# RX8I.net
KiCad netlist of a schematic drawn in EAGLE
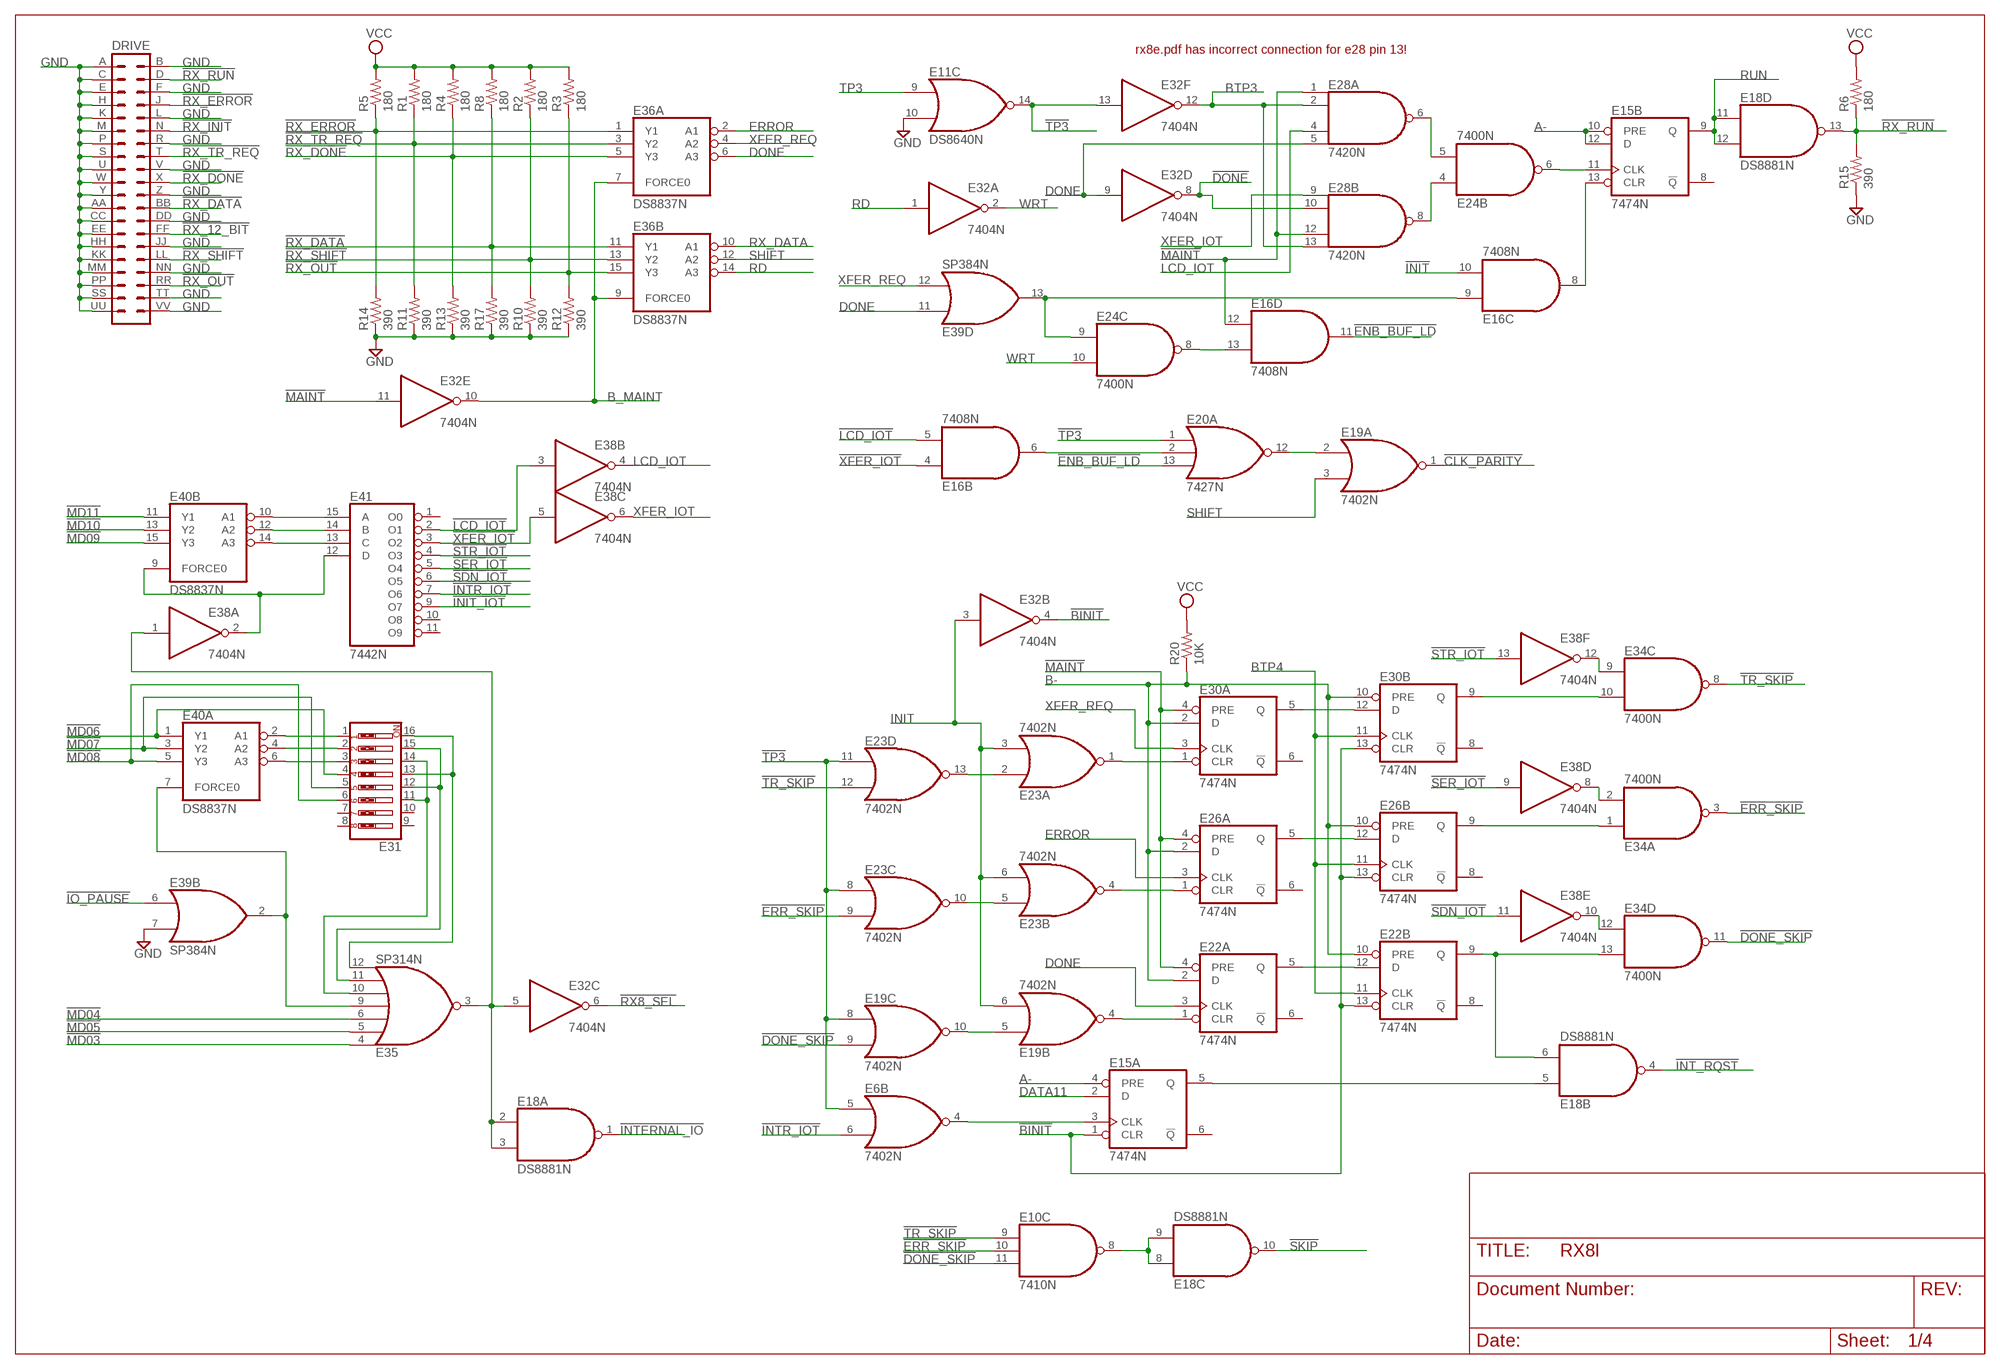
[diagram p0: schematic, sheet 1]
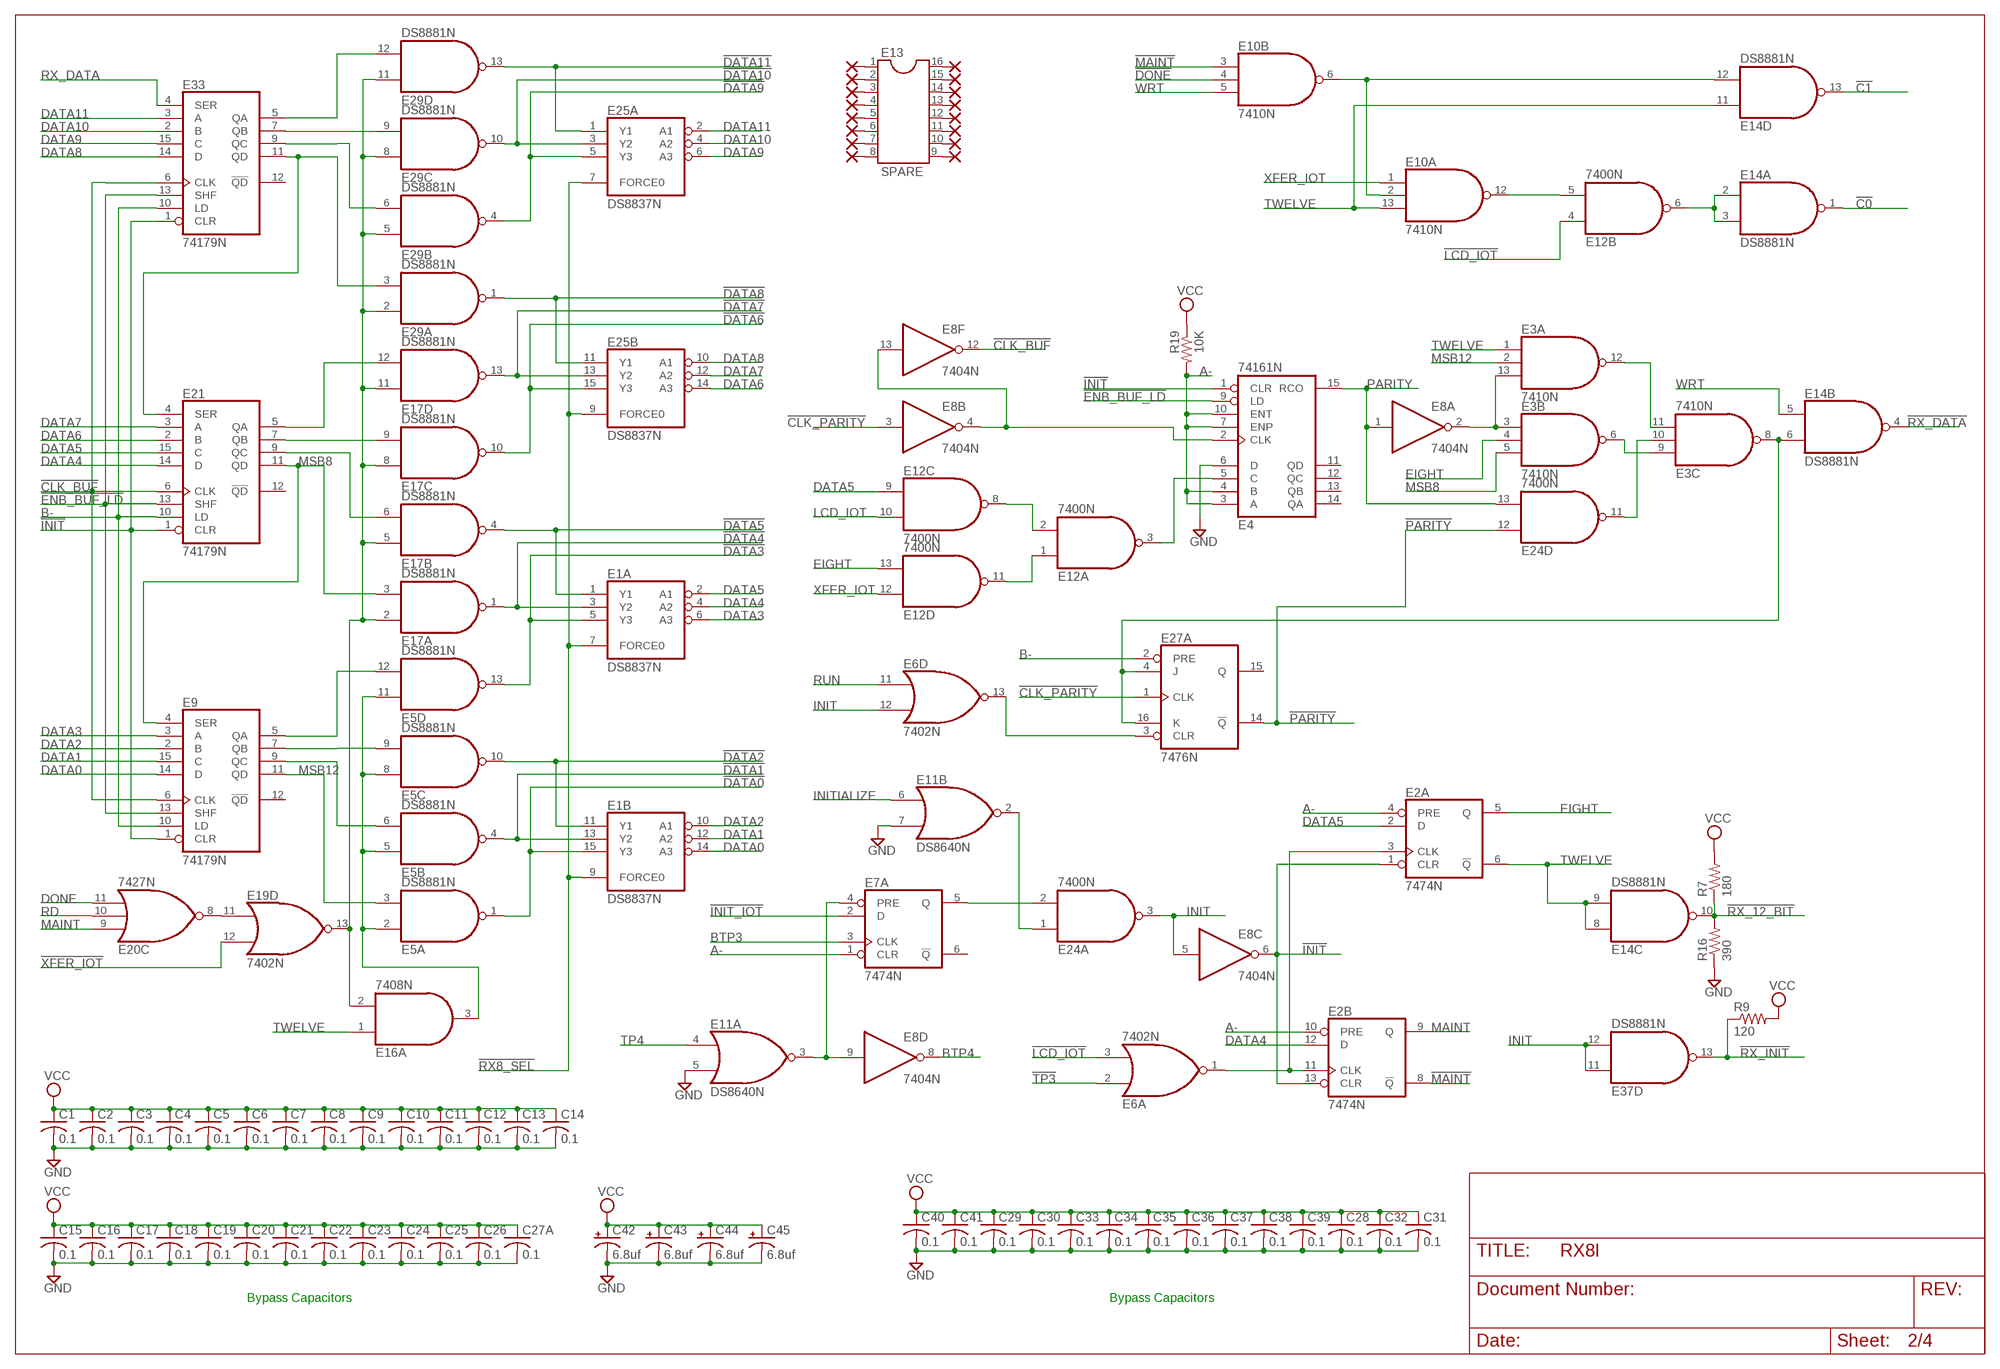
[diagram p1: schematic, sheet 2]
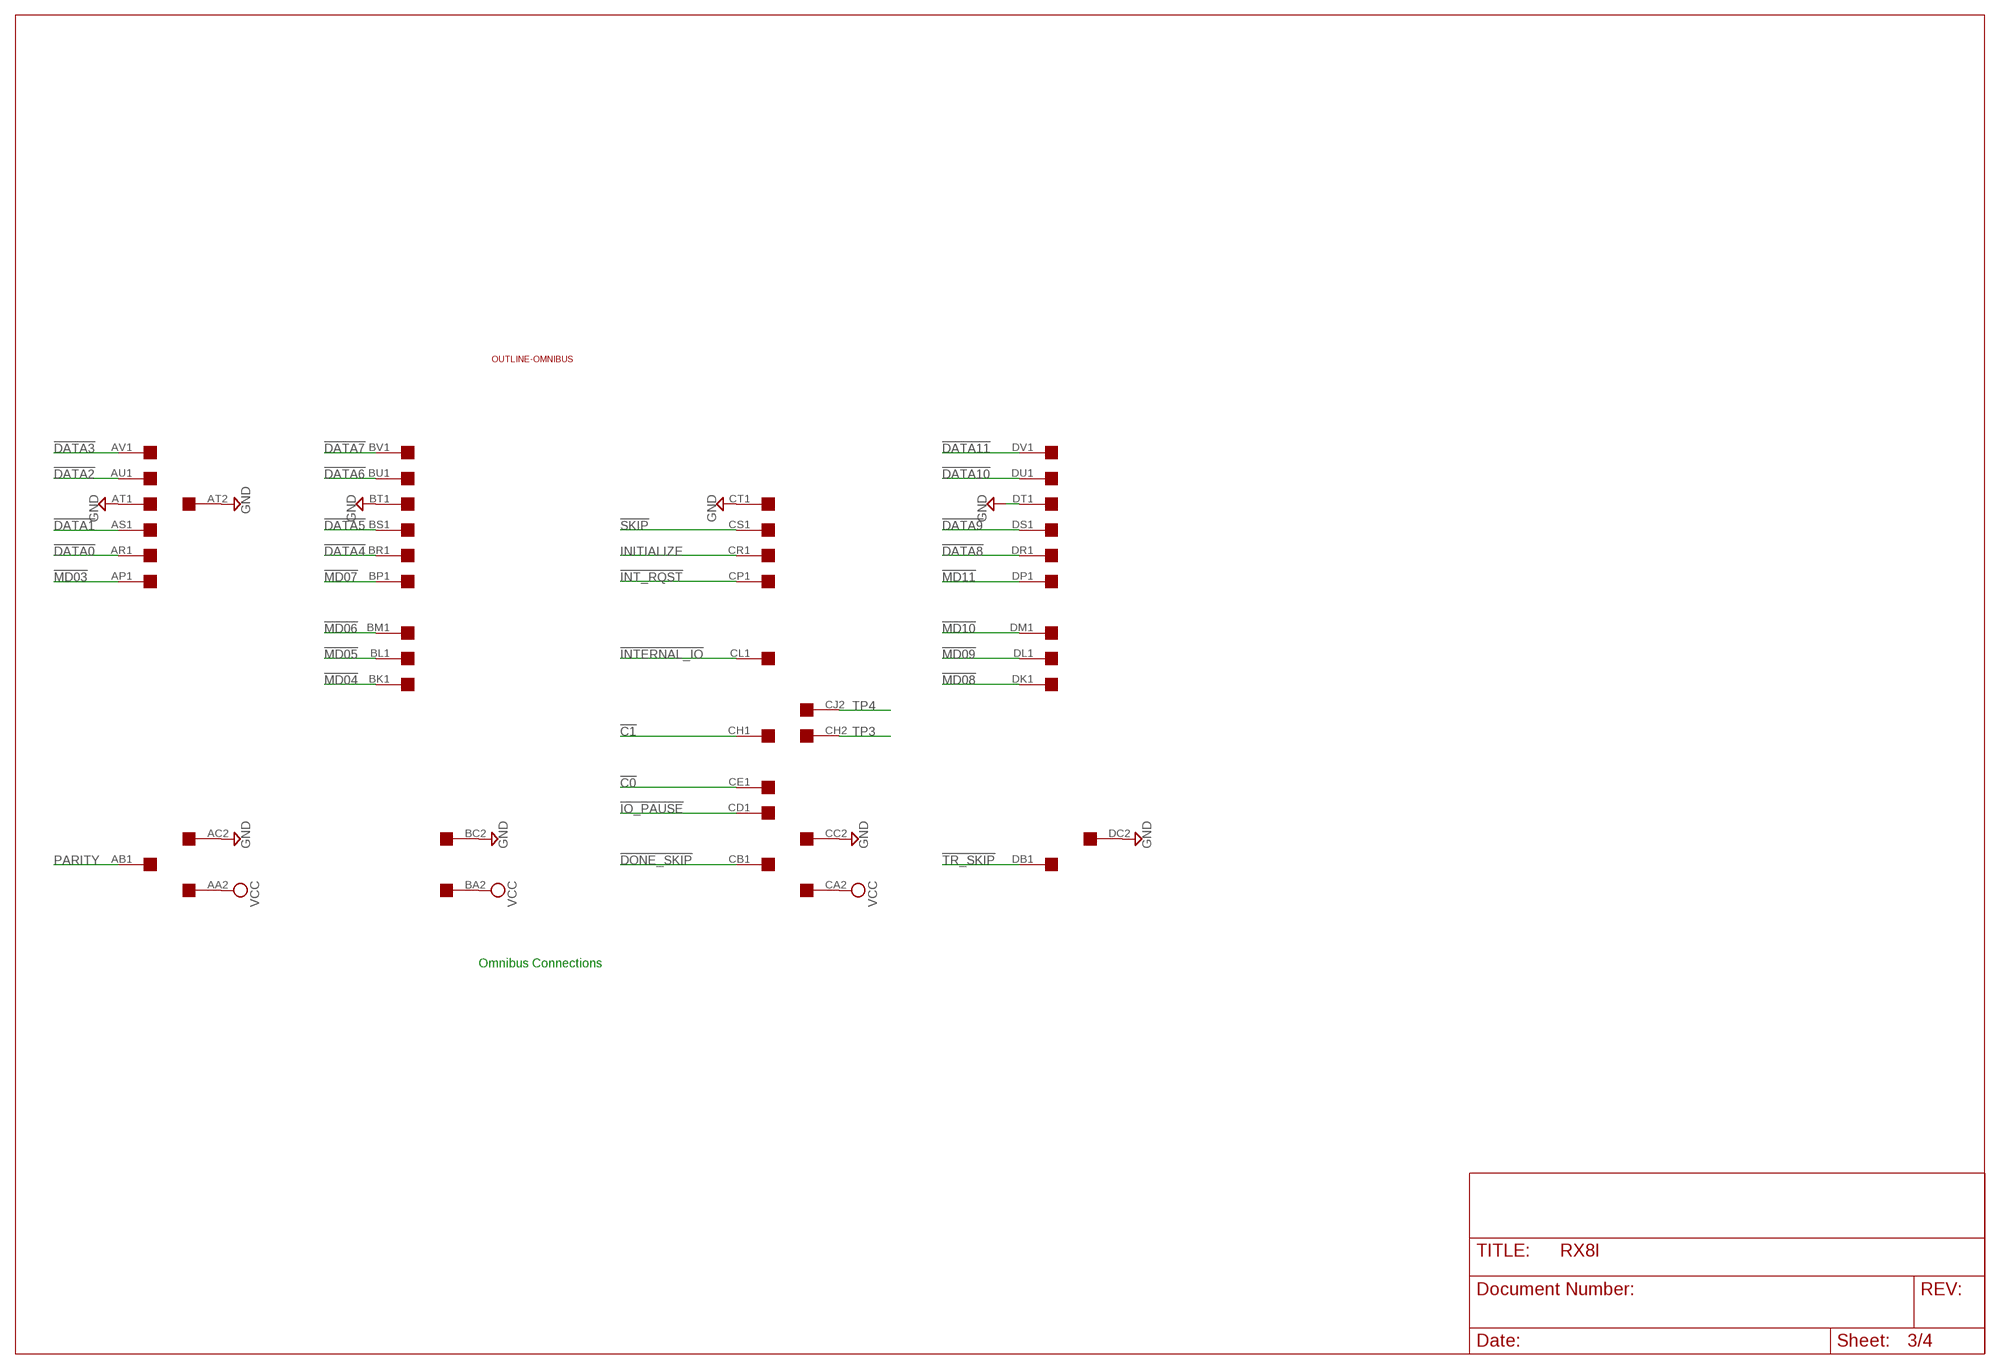
[diagram p2: schematic, sheet 3]
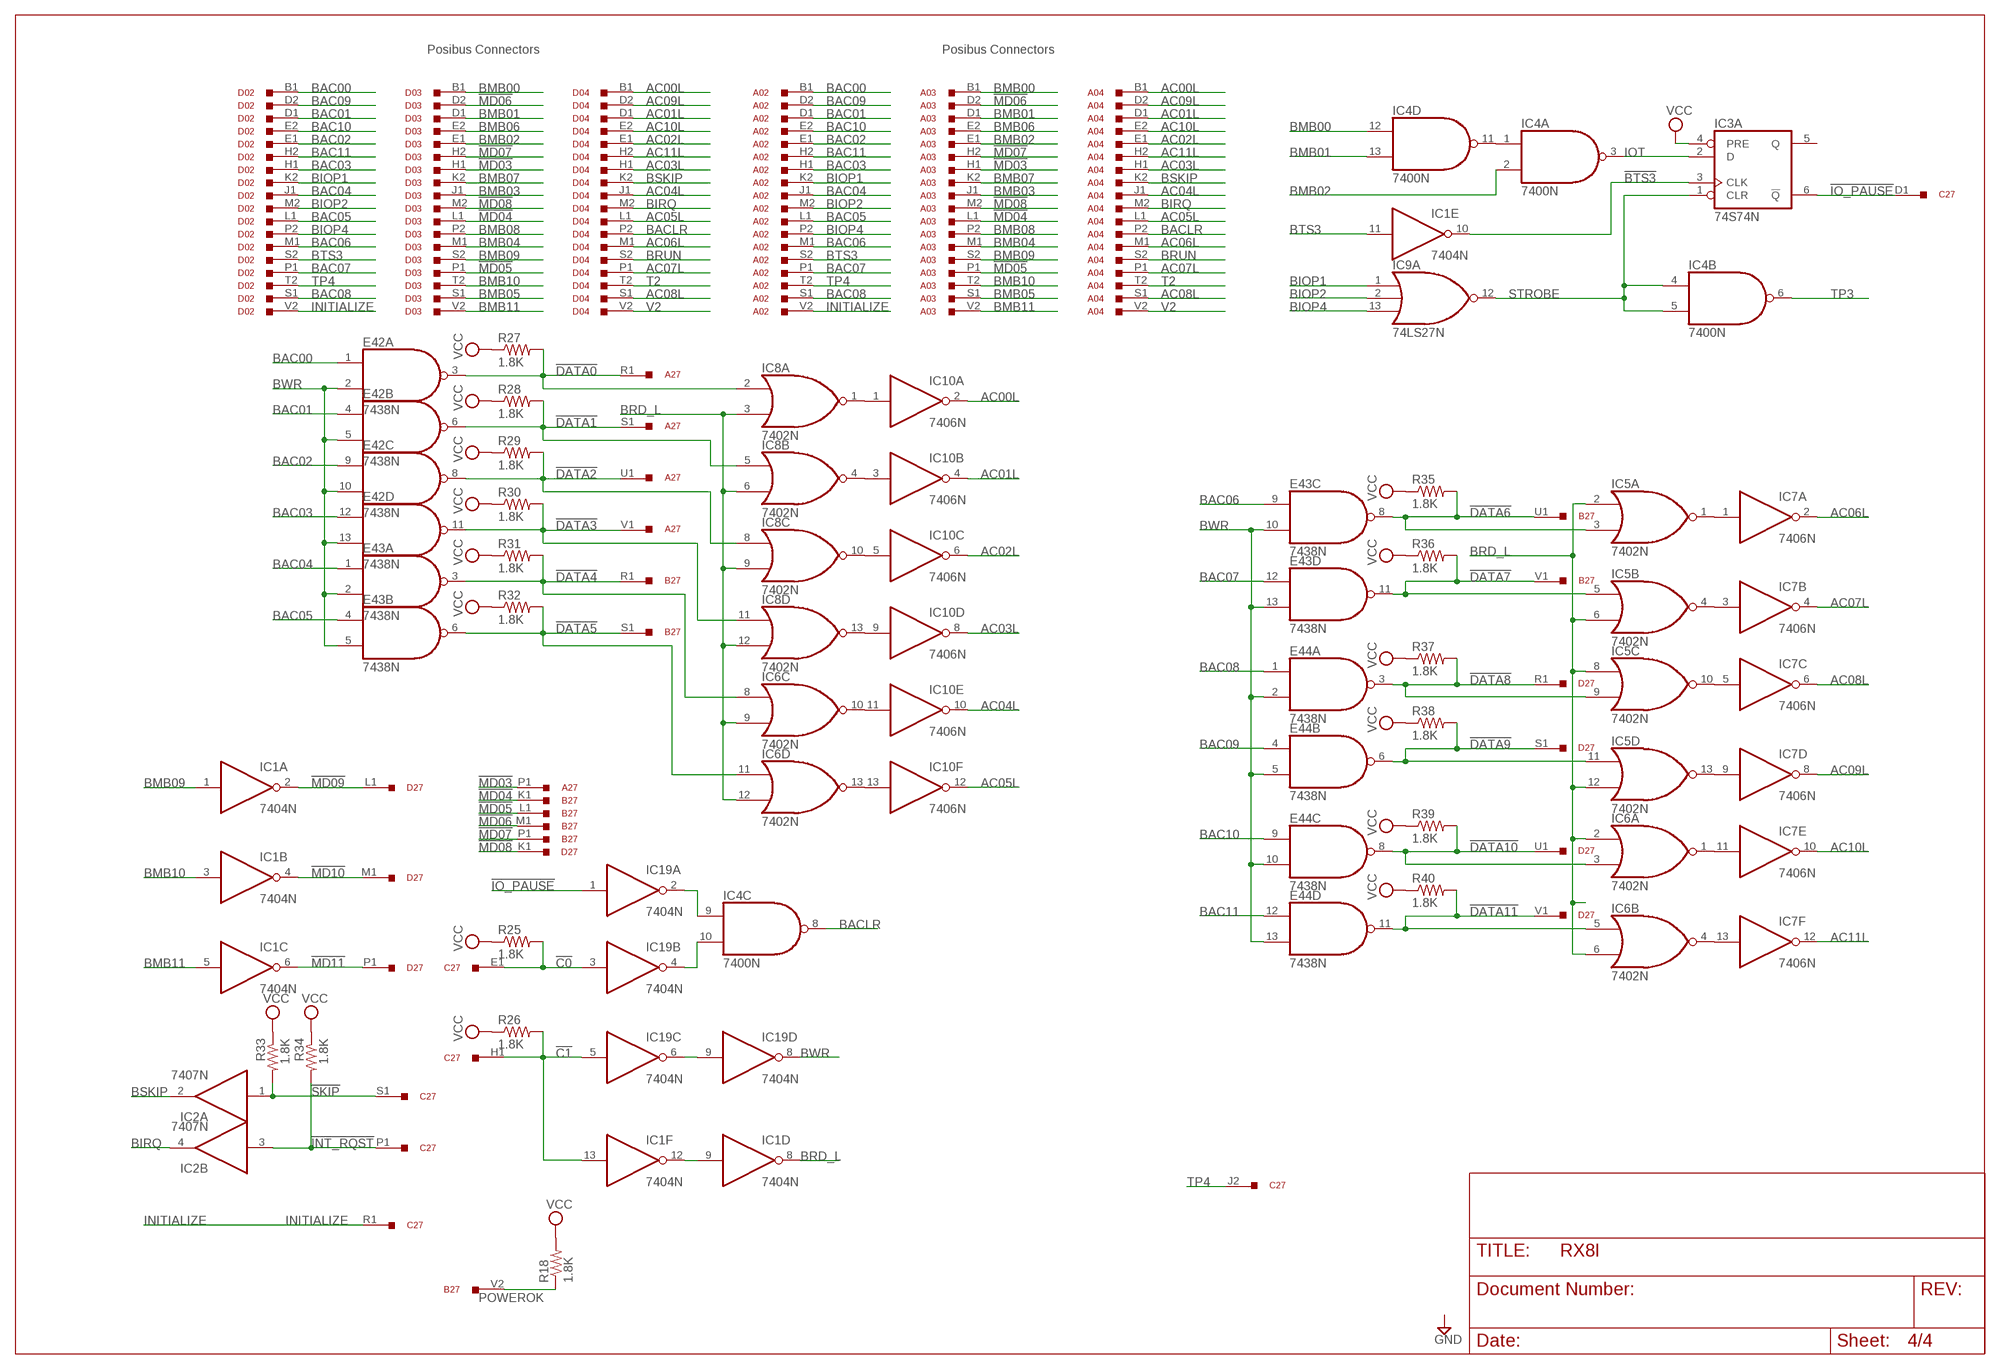
[diagram p3: schematic, sheet 4]

(export (version "E")
  (design (tool "Eeschema 10.0.6"))
  (components
    (comp (ref "U$2")
      (value "QUAD")
      (footprint "eagle-import:EDGE-CON8")
      (libsource (lib "eagle-import") (part "QUAD"))
    )
    (comp (ref "U$5")
      (value "OUTLINE-OMNIBUS")
      (footprint "eagle-import:OMNIBUS")
      (libsource (lib "eagle-import") (part "OUTLINE-OMNIBUS"))
    )
    (comp (ref "A02")
      (value "M903")
      (footprint "eagle-import:H807")
      (libsource (lib "eagle-import") (part "M903"))
    )
    (comp (ref "A03")
      (value "M903")
      (footprint "eagle-import:H807")
      (libsource (lib "eagle-import") (part "M903"))
    )
    (comp (ref "A04")
      (value "M903")
      (footprint "eagle-import:H807")
      (libsource (lib "eagle-import") (part "M903"))
    )
    (comp (ref "A27")
      (value "M916")
      (footprint "eagle-import:H807")
      (libsource (lib "eagle-import") (part "M916"))
    )
    (comp (ref "B27")
      (value "M916")
      (footprint "eagle-import:H807")
      (libsource (lib "eagle-import") (part "M916"))
    )
    (comp (ref "C27")
      (value "M916")
      (footprint "eagle-import:H807")
      (libsource (lib "eagle-import") (part "M916"))
    )
    (comp (ref "D02")
      (value "M903")
      (footprint "eagle-import:H807")
      (libsource (lib "eagle-import") (part "M903"))
    )
    (comp (ref "D03")
      (value "M903")
      (footprint "eagle-import:H807")
      (libsource (lib "eagle-import") (part "M903"))
    )
    (comp (ref "D04")
      (value "M903")
      (footprint "eagle-import:H807")
      (libsource (lib "eagle-import") (part "M903"))
    )
    (comp (ref "D27")
      (value "M916")
      (footprint "eagle-import:H807")
      (libsource (lib "eagle-import") (part "M916"))
    )
    (comp (ref "E42")
      (value "7438N")
      (footprint "eagle-import:DIL14")
      (libsource (lib "eagle-import") (part "7438N"))
    )
    (comp (ref "E43")
      (value "7438N")
      (footprint "eagle-import:DIL14")
      (libsource (lib "eagle-import") (part "7438N"))
    )
    (comp (ref "E44")
      (value "7438N")
      (footprint "eagle-import:DIL14")
      (libsource (lib "eagle-import") (part "7438N"))
    )
    (comp (ref "IC1")
      (value "7404N")
      (footprint "eagle-import:DIL14")
      (libsource (lib "eagle-import") (part "7404N"))
    )
    (comp (ref "IC2")
      (value "7407N")
      (footprint "eagle-import:DIL14")
      (libsource (lib "eagle-import") (part "7407N"))
    )
    (comp (ref "IC3")
      (value "74S74N")
      (footprint "eagle-import:DIL14")
      (libsource (lib "eagle-import") (part "7474NS"))
    )
    (comp (ref "IC4")
      (value "7400N")
      (footprint "eagle-import:DIL14")
      (libsource (lib "eagle-import") (part "7400N"))
    )
    (comp (ref "IC5")
      (value "7402N")
      (footprint "eagle-import:DIL14")
      (libsource (lib "eagle-import") (part "7402N"))
    )
    (comp (ref "IC6")
      (value "7402N")
      (footprint "eagle-import:DIL14")
      (libsource (lib "eagle-import") (part "7402N"))
    )
    (comp (ref "IC7")
      (value "7406N")
      (footprint "eagle-import:DIL14")
      (libsource (lib "eagle-import") (part "7406N"))
    )
    (comp (ref "IC8")
      (value "7402N")
      (footprint "eagle-import:DIL14")
      (libsource (lib "eagle-import") (part "7402N"))
    )
    (comp (ref "IC9")
      (value "74LS27N")
      (footprint "eagle-import:DIL14")
      (libsource (lib "eagle-import") (part "7427NLS"))
    )
    (comp (ref "IC10")
      (value "7406N")
      (footprint "eagle-import:DIL14")
      (libsource (lib "eagle-import") (part "7406N"))
    )
    (comp (ref "IC19")
      (value "7404N")
      (footprint "eagle-import:DIL14")
      (libsource (lib "eagle-import") (part "7404N"))
    )
    (comp (ref "R18")
      (value "1.8K")
      (footprint "eagle-import:0207_10")
      (libsource (lib "eagle-import") (part "R-US_0207/10"))
    )
    (comp (ref "R25")
      (value "1.8K")
      (footprint "eagle-import:0207_10")
      (libsource (lib "eagle-import") (part "R-US_0207/10"))
    )
    (comp (ref "R26")
      (value "1.8K")
      (footprint "eagle-import:0207_10")
      (libsource (lib "eagle-import") (part "R-US_0207/10"))
    )
    (comp (ref "R27")
      (value "1.8K")
      (footprint "eagle-import:0207_10")
      (libsource (lib "eagle-import") (part "R-US_0207/10"))
    )
    (comp (ref "R28")
      (value "1.8K")
      (footprint "eagle-import:0207_10")
      (libsource (lib "eagle-import") (part "R-US_0207/10"))
    )
    (comp (ref "R29")
      (value "1.8K")
      (footprint "eagle-import:0207_10")
      (libsource (lib "eagle-import") (part "R-US_0207/10"))
    )
    (comp (ref "R30")
      (value "1.8K")
      (footprint "eagle-import:0207_10")
      (libsource (lib "eagle-import") (part "R-US_0207/10"))
    )
    (comp (ref "R31")
      (value "1.8K")
      (footprint "eagle-import:0207_10")
      (libsource (lib "eagle-import") (part "R-US_0207/10"))
    )
    (comp (ref "R32")
      (value "1.8K")
      (footprint "eagle-import:0207_10")
      (libsource (lib "eagle-import") (part "R-US_0207/10"))
    )
    (comp (ref "R33")
      (value "1.8K")
      (footprint "eagle-import:0207_10")
      (libsource (lib "eagle-import") (part "R-US_0207/10"))
    )
    (comp (ref "R34")
      (value "1.8K")
      (footprint "eagle-import:0207_10")
      (libsource (lib "eagle-import") (part "R-US_0207/10"))
    )
    (comp (ref "R35")
      (value "1.8K")
      (footprint "eagle-import:0207_10")
      (libsource (lib "eagle-import") (part "R-US_0207/10"))
    )
    (comp (ref "R36")
      (value "1.8K")
      (footprint "eagle-import:0207_10")
      (libsource (lib "eagle-import") (part "R-US_0207/10"))
    )
    (comp (ref "R37")
      (value "1.8K")
      (footprint "eagle-import:0207_10")
      (libsource (lib "eagle-import") (part "R-US_0207/10"))
    )
    (comp (ref "R38")
      (value "1.8K")
      (footprint "eagle-import:0207_10")
      (libsource (lib "eagle-import") (part "R-US_0207/10"))
    )
    (comp (ref "R39")
      (value "1.8K")
      (footprint "eagle-import:0207_10")
      (libsource (lib "eagle-import") (part "R-US_0207/10"))
    )
    (comp (ref "R40")
      (value "1.8K")
      (footprint "eagle-import:0207_10")
      (libsource (lib "eagle-import") (part "R-US_0207/10"))
    )
    (comp (ref "DRIVE")
      (value "DEC40PINH")
      (footprint "eagle-import:DEC40PINH")
      (libsource (lib "eagle-import") (part "DEC40PINH"))
    )
    (comp (ref "E6")
      (value "7402N")
      (footprint "eagle-import:DIL14")
      (libsource (lib "eagle-import") (part "7402NLS"))
    )
    (comp (ref "E10")
      (value "7410N")
      (footprint "eagle-import:DIL14")
      (libsource (lib "eagle-import") (part "7410NLS"))
    )
    (comp (ref "E11")
      (value "DS8640N")
      (footprint "eagle-import:DIL14")
      (libsource (lib "eagle-import") (part "DS8640N"))
    )
    (comp (ref "E15")
      (value "7474N")
      (footprint "eagle-import:DIL14")
      (libsource (lib "eagle-import") (part "7474NLS"))
    )
    (comp (ref "E16")
      (value "7408N")
      (footprint "eagle-import:DIL14")
      (libsource (lib "eagle-import") (part "7408NLS"))
    )
    (comp (ref "E18")
      (value "DS8881N")
      (footprint "eagle-import:DIL14")
      (libsource (lib "eagle-import") (part "7401NLS"))
    )
    (comp (ref "E19")
      (value "7402N")
      (footprint "eagle-import:DIL14")
      (libsource (lib "eagle-import") (part "7402NLS"))
    )
    (comp (ref "E20")
      (value "7427N")
      (footprint "eagle-import:DIL14")
      (libsource (lib "eagle-import") (part "7427NLS"))
    )
    (comp (ref "E22")
      (value "7474N")
      (footprint "eagle-import:DIL14")
      (libsource (lib "eagle-import") (part "7474NLS"))
    )
    (comp (ref "E23")
      (value "7402N")
      (footprint "eagle-import:DIL14")
      (libsource (lib "eagle-import") (part "7402NLS"))
    )
    (comp (ref "E24")
      (value "7400N")
      (footprint "eagle-import:DIL14")
      (libsource (lib "eagle-import") (part "7400NLS"))
    )
    (comp (ref "E26")
      (value "7474N")
      (footprint "eagle-import:DIL14")
      (libsource (lib "eagle-import") (part "7474NLS"))
    )
    (comp (ref "E28")
      (value "7420N")
      (footprint "eagle-import:DIL14")
      (libsource (lib "eagle-import") (part "7420NLS"))
    )
    (comp (ref "E30")
      (value "7474N")
      (footprint "eagle-import:DIL14")
      (libsource (lib "eagle-import") (part "7474NLS"))
    )
    (comp (ref "E31")
      (value "SW_DIP-8")
      (footprint "eagle-import:EDG-08")
      (libsource (lib "eagle-import") (part "SW_DIP-8"))
    )
    (comp (ref "E32")
      (value "7404N")
      (footprint "eagle-import:DIL14")
      (libsource (lib "eagle-import") (part "7404NLS"))
    )
    (comp (ref "E34")
      (value "7400N")
      (footprint "eagle-import:DIL14")
      (libsource (lib "eagle-import") (part "7400N"))
    )
    (comp (ref "E35")
      (value "SP314N")
      (footprint "eagle-import:DIL14")
      (libsource (lib "eagle-import") (part "SP314N"))
    )
    (comp (ref "E36")
      (value "DS8837N")
      (footprint "eagle-import:DIL16")
      (libsource (lib "eagle-import") (part "DS8837N"))
    )
    (comp (ref "E38")
      (value "7404N")
      (footprint "eagle-import:DIL14")
      (libsource (lib "eagle-import") (part "7404NLS"))
    )
    (comp (ref "E39")
      (value "SP384N")
      (footprint "eagle-import:DIL14")
      (libsource (lib "eagle-import") (part "SP384N"))
    )
    (comp (ref "E40")
      (value "DS8837N")
      (footprint "eagle-import:DIL16")
      (libsource (lib "eagle-import") (part "DS8837N"))
    )
    (comp (ref "E41")
      (value "7442N")
      (footprint "eagle-import:DIL16")
      (libsource (lib "eagle-import") (part "7442NLS"))
    )
    (comp (ref "R1")
      (value "180")
      (footprint "eagle-import:0207_10")
      (libsource (lib "eagle-import") (part "R-US_0207/10"))
    )
    (comp (ref "R2")
      (value "180")
      (footprint "eagle-import:0207_10")
      (libsource (lib "eagle-import") (part "R-US_0207/10"))
    )
    (comp (ref "R3")
      (value "180")
      (footprint "eagle-import:0207_10")
      (libsource (lib "eagle-import") (part "R-US_0207/10"))
    )
    (comp (ref "R4")
      (value "180")
      (footprint "eagle-import:0207_10")
      (libsource (lib "eagle-import") (part "R-US_0207/10"))
    )
    (comp (ref "R5")
      (value "180")
      (footprint "eagle-import:0207_10")
      (libsource (lib "eagle-import") (part "R-US_0207/10"))
    )
    (comp (ref "R6")
      (value "180")
      (footprint "eagle-import:0207_10")
      (libsource (lib "eagle-import") (part "R-US_0207/10"))
    )
    (comp (ref "R8")
      (value "180")
      (footprint "eagle-import:0207_10")
      (libsource (lib "eagle-import") (part "R-US_0207/10"))
    )
    (comp (ref "R10")
      (value "390")
      (footprint "eagle-import:0207_10")
      (libsource (lib "eagle-import") (part "R-US_0207/10"))
    )
    (comp (ref "R11")
      (value "390")
      (footprint "eagle-import:0207_10")
      (libsource (lib "eagle-import") (part "R-US_0207/10"))
    )
    (comp (ref "R12")
      (value "390")
      (footprint "eagle-import:0207_10")
      (libsource (lib "eagle-import") (part "R-US_0207/10"))
    )
    (comp (ref "R13")
      (value "390")
      (footprint "eagle-import:0207_10")
      (libsource (lib "eagle-import") (part "R-US_0207/10"))
    )
    (comp (ref "R14")
      (value "390")
      (footprint "eagle-import:0207_10")
      (libsource (lib "eagle-import") (part "R-US_0207/10"))
    )
    (comp (ref "R15")
      (value "390")
      (footprint "eagle-import:0207_10")
      (libsource (lib "eagle-import") (part "R-US_0207/10"))
    )
    (comp (ref "R17")
      (value "390")
      (footprint "eagle-import:0207_10")
      (libsource (lib "eagle-import") (part "R-US_0207/10"))
    )
    (comp (ref "R20")
      (value "10K")
      (footprint "eagle-import:0207_10")
      (libsource (lib "eagle-import") (part "R-US_0207/10"))
    )
    (comp (ref "C1")
      (value "0.1")
      (footprint "eagle-import:C050-025X075")
      (libsource (lib "eagle-import") (part "C-US050-025X075"))
    )
    (comp (ref "C2")
      (value "0.1")
      (footprint "eagle-import:C050-025X075")
      (libsource (lib "eagle-import") (part "C-US050-025X075"))
    )
    (comp (ref "C3")
      (value "0.1")
      (footprint "eagle-import:C050-025X075")
      (libsource (lib "eagle-import") (part "C-US050-025X075"))
    )
    (comp (ref "C4")
      (value "0.1")
      (footprint "eagle-import:C050-025X075")
      (libsource (lib "eagle-import") (part "C-US050-025X075"))
    )
    (comp (ref "C5")
      (value "0.1")
      (footprint "eagle-import:C050-025X075")
      (libsource (lib "eagle-import") (part "C-US050-025X075"))
    )
    (comp (ref "C6")
      (value "0.1")
      (footprint "eagle-import:C050-025X075")
      (libsource (lib "eagle-import") (part "C-US050-025X075"))
    )
    (comp (ref "C7")
      (value "0.1")
      (footprint "eagle-import:C050-025X075")
      (libsource (lib "eagle-import") (part "C-US050-025X075"))
    )
    (comp (ref "C8")
      (value "0.1")
      (footprint "eagle-import:C050-025X075")
      (libsource (lib "eagle-import") (part "C-US050-025X075"))
    )
    (comp (ref "C9")
      (value "0.1")
      (footprint "eagle-import:C050-025X075")
      (libsource (lib "eagle-import") (part "C-US050-025X075"))
    )
    (comp (ref "C10")
      (value "0.1")
      (footprint "eagle-import:C050-025X075")
      (libsource (lib "eagle-import") (part "C-US050-025X075"))
    )
    (comp (ref "C11")
      (value "0.1")
      (footprint "eagle-import:C050-025X075")
      (libsource (lib "eagle-import") (part "C-US050-025X075"))
    )
    (comp (ref "C12")
      (value "0.1")
      (footprint "eagle-import:C050-025X075")
      (libsource (lib "eagle-import") (part "C-US050-025X075"))
    )
    (comp (ref "C13")
      (value "0.1")
      (footprint "eagle-import:C050-025X075")
      (libsource (lib "eagle-import") (part "C-US050-025X075"))
    )
    (comp (ref "C14")
      (value "0.1")
      (footprint "eagle-import:C050-025X075")
      (libsource (lib "eagle-import") (part "C-US050-025X075"))
    )
    (comp (ref "C15")
      (value "0.1")
      (footprint "eagle-import:C050-025X075")
      (libsource (lib "eagle-import") (part "C-US050-025X075"))
    )
    (comp (ref "C16")
      (value "0.1")
      (footprint "eagle-import:C050-025X075")
      (libsource (lib "eagle-import") (part "C-US050-025X075"))
    )
    (comp (ref "C17")
      (value "0.1")
      (footprint "eagle-import:C050-025X075")
      (libsource (lib "eagle-import") (part "C-US050-025X075"))
    )
    (comp (ref "C18")
      (value "0.1")
      (footprint "eagle-import:C050-025X075")
      (libsource (lib "eagle-import") (part "C-US050-025X075"))
    )
    (comp (ref "C19")
      (value "0.1")
      (footprint "eagle-import:C050-025X075")
      (libsource (lib "eagle-import") (part "C-US050-025X075"))
    )
    (comp (ref "C20")
      (value "0.1")
      (footprint "eagle-import:C050-025X075")
      (libsource (lib "eagle-import") (part "C-US050-025X075"))
    )
    (comp (ref "C21")
      (value "0.1")
      (footprint "eagle-import:C050-025X075")
      (libsource (lib "eagle-import") (part "C-US050-025X075"))
    )
    (comp (ref "C22")
      (value "0.1")
      (footprint "eagle-import:C050-025X075")
      (libsource (lib "eagle-import") (part "C-US050-025X075"))
    )
    (comp (ref "C23")
      (value "0.1")
      (footprint "eagle-import:C050-025X075")
      (libsource (lib "eagle-import") (part "C-US050-025X075"))
    )
    (comp (ref "C24")
      (value "0.1")
      (footprint "eagle-import:C050-025X075")
      (libsource (lib "eagle-import") (part "C-US050-025X075"))
    )
    (comp (ref "C25")
      (value "0.1")
      (footprint "eagle-import:C050-025X075")
      (libsource (lib "eagle-import") (part "C-US050-025X075"))
    )
    (comp (ref "C26")
      (value "0.1")
      (footprint "eagle-import:C050-025X075")
      (libsource (lib "eagle-import") (part "C-US050-025X075"))
    )
    (comp (ref "C27A")
      (value "0.1")
      (footprint "eagle-import:C050-025X075")
      (libsource (lib "eagle-import") (part "C-US050-025X075"))
    )
    (comp (ref "C28")
      (value "0.1")
      (footprint "eagle-import:C050-025X075")
      (libsource (lib "eagle-import") (part "C-US050-025X075"))
    )
    (comp (ref "C29")
      (value "0.1")
      (footprint "eagle-import:C050-025X075")
      (libsource (lib "eagle-import") (part "C-US050-025X075"))
    )
    (comp (ref "C30")
      (value "0.1")
      (footprint "eagle-import:C050-025X075")
      (libsource (lib "eagle-import") (part "C-US050-025X075"))
    )
    (comp (ref "C31")
      (value "0.1")
      (footprint "eagle-import:C050-025X075")
      (libsource (lib "eagle-import") (part "C-US050-025X075"))
    )
    (comp (ref "C32")
      (value "0.1")
      (footprint "eagle-import:C050-025X075")
      (libsource (lib "eagle-import") (part "C-US050-025X075"))
    )
    (comp (ref "C33")
      (value "0.1")
      (footprint "eagle-import:C050-025X075")
      (libsource (lib "eagle-import") (part "C-US050-025X075"))
    )
    (comp (ref "C34")
      (value "0.1")
      (footprint "eagle-import:C050-025X075")
      (libsource (lib "eagle-import") (part "C-US050-025X075"))
    )
    (comp (ref "C35")
      (value "0.1")
      (footprint "eagle-import:C050-025X075")
      (libsource (lib "eagle-import") (part "C-US050-025X075"))
    )
    (comp (ref "C36")
      (value "0.1")
      (footprint "eagle-import:C050-025X075")
      (libsource (lib "eagle-import") (part "C-US050-025X075"))
    )
    (comp (ref "C37")
      (value "0.1")
      (footprint "eagle-import:C050-025X075")
      (libsource (lib "eagle-import") (part "C-US050-025X075"))
    )
    (comp (ref "C38")
      (value "0.1")
      (footprint "eagle-import:C050-025X075")
      (libsource (lib "eagle-import") (part "C-US050-025X075"))
    )
    (comp (ref "C39")
      (value "0.1")
      (footprint "eagle-import:C050-025X075")
      (libsource (lib "eagle-import") (part "C-US050-025X075"))
    )
    (comp (ref "C40")
      (value "0.1")
      (footprint "eagle-import:C050-025X075")
      (libsource (lib "eagle-import") (part "C-US050-025X075"))
    )
    (comp (ref "C41")
      (value "0.1")
      (footprint "eagle-import:C050-025X075")
      (libsource (lib "eagle-import") (part "C-US050-025X075"))
    )
    (comp (ref "C42")
      (value "6.8uf")
      (footprint "eagle-import:E22-6")
      (libsource (lib "eagle-import") (part "CPOL-USE22-6AXIAL"))
    )
    (comp (ref "C43")
      (value "6.8uf")
      (footprint "eagle-import:E22-6")
      (libsource (lib "eagle-import") (part "CPOL-USE22-6AXIAL"))
    )
    (comp (ref "C44")
      (value "6.8uf")
      (footprint "eagle-import:E22-6")
      (libsource (lib "eagle-import") (part "CPOL-USE22-6AXIAL"))
    )
    (comp (ref "C45")
      (value "6.8uf")
      (footprint "eagle-import:E22-6")
      (libsource (lib "eagle-import") (part "CPOL-USE22-6AXIAL"))
    )
    (comp (ref "E1")
      (value "DS8837N")
      (footprint "eagle-import:DIL16")
      (libsource (lib "eagle-import") (part "DS8837N"))
    )
    (comp (ref "E2")
      (value "7474N")
      (footprint "eagle-import:DIL14")
      (libsource (lib "eagle-import") (part "7474NLS"))
    )
    (comp (ref "E3")
      (value "7410N")
      (footprint "eagle-import:DIL14")
      (libsource (lib "eagle-import") (part "7410NLS"))
    )
    (comp (ref "E4")
      (value "74161N")
      (footprint "eagle-import:DIL16")
      (libsource (lib "eagle-import") (part "74161N"))
    )
    (comp (ref "E5")
      (value "DS8881N")
      (footprint "eagle-import:DIL14")
      (libsource (lib "eagle-import") (part "7401NLS"))
    )
    (comp (ref "E7")
      (value "7474N")
      (footprint "eagle-import:DIL14")
      (libsource (lib "eagle-import") (part "7474NLS"))
    )
    (comp (ref "E8")
      (value "7404N")
      (footprint "eagle-import:DIL14")
      (libsource (lib "eagle-import") (part "7404NLS"))
    )
    (comp (ref "E9")
      (value "74179N")
      (footprint "eagle-import:DIL16")
      (libsource (lib "eagle-import") (part "74179N"))
    )
    (comp (ref "E12")
      (value "7400N")
      (footprint "eagle-import:DIL14")
      (libsource (lib "eagle-import") (part "7400NLS"))
    )
    (comp (ref "E13")
      (value "SPARE")
      (footprint "eagle-import:DIL16")
      (libsource (lib "eagle-import") (part "DIL16"))
    )
    (comp (ref "E14")
      (value "DS8881N")
      (footprint "eagle-import:DIL14")
      (libsource (lib "eagle-import") (part "7401NLS"))
    )
    (comp (ref "E17")
      (value "DS8881N")
      (footprint "eagle-import:DIL14")
      (libsource (lib "eagle-import") (part "7401NLS"))
    )
    (comp (ref "E21")
      (value "74179N")
      (footprint "eagle-import:DIL16")
      (libsource (lib "eagle-import") (part "74179N"))
    )
    (comp (ref "E25")
      (value "DS8837N")
      (footprint "eagle-import:DIL16")
      (libsource (lib "eagle-import") (part "DS8837N"))
    )
    (comp (ref "E27")
      (value "7476N")
      (footprint "eagle-import:DIL16")
      (libsource (lib "eagle-import") (part "7476N"))
    )
    (comp (ref "E29")
      (value "DS8881N")
      (footprint "eagle-import:DIL14")
      (libsource (lib "eagle-import") (part "7401NLS"))
    )
    (comp (ref "E33")
      (value "74179N")
      (footprint "eagle-import:DIL16")
      (libsource (lib "eagle-import") (part "74179N"))
    )
    (comp (ref "E37")
      (value "DS8881N")
      (footprint "eagle-import:DIL14")
      (libsource (lib "eagle-import") (part "7401NLS"))
    )
    (comp (ref "PAD10")
      (value "1,6/0,8")
      (footprint "eagle-import:1,6_0,8")
      (libsource (lib "eagle-import") (part "1,6/0,8"))
    )
    (comp (ref "PAD11")
      (value "1,6/0,8")
      (footprint "eagle-import:1,6_0,8")
      (libsource (lib "eagle-import") (part "1,6/0,8"))
    )
    (comp (ref "PAD12")
      (value "1,6/0,8")
      (footprint "eagle-import:1,6_0,8")
      (libsource (lib "eagle-import") (part "1,6/0,8"))
    )
    (comp (ref "PAD13")
      (value "1,6/0,8")
      (footprint "eagle-import:1,6_0,8")
      (libsource (lib "eagle-import") (part "1,6/0,8"))
    )
    (comp (ref "PAD14")
      (value "1,6/0,8")
      (footprint "eagle-import:1,6_0,8")
      (libsource (lib "eagle-import") (part "1,6/0,8"))
    )
    (comp (ref "PAD15")
      (value "1,6/0,8")
      (footprint "eagle-import:1,6_0,8")
      (libsource (lib "eagle-import") (part "1,6/0,8"))
    )
    (comp (ref "PAD16")
      (value "1,6/0,8")
      (footprint "eagle-import:1,6_0,8")
      (libsource (lib "eagle-import") (part "1,6/0,8"))
    )
    (comp (ref "PAD17")
      (value "1,6/0,8")
      (footprint "eagle-import:1,6_0,8")
      (libsource (lib "eagle-import") (part "1,6/0,8"))
    )
    (comp (ref "PAD20")
      (value "1,6/0,8")
      (footprint "eagle-import:1,6_0,8")
      (libsource (lib "eagle-import") (part "1,6/0,8"))
    )
    (comp (ref "PAD21")
      (value "1,6/0,8")
      (footprint "eagle-import:1,6_0,8")
      (libsource (lib "eagle-import") (part "1,6/0,8"))
    )
    (comp (ref "PAD22")
      (value "1,6/0,8")
      (footprint "eagle-import:1,6_0,8")
      (libsource (lib "eagle-import") (part "1,6/0,8"))
    )
    (comp (ref "PAD23")
      (value "1,6/0,8")
      (footprint "eagle-import:1,6_0,8")
      (libsource (lib "eagle-import") (part "1,6/0,8"))
    )
    (comp (ref "PAD24")
      (value "1,6/0,8")
      (footprint "eagle-import:1,6_0,8")
      (libsource (lib "eagle-import") (part "1,6/0,8"))
    )
    (comp (ref "PAD25")
      (value "1,6/0,8")
      (footprint "eagle-import:1,6_0,8")
      (libsource (lib "eagle-import") (part "1,6/0,8"))
    )
    (comp (ref "PAD26")
      (value "1,6/0,8")
      (footprint "eagle-import:1,6_0,8")
      (libsource (lib "eagle-import") (part "1,6/0,8"))
    )
    (comp (ref "PAD27")
      (value "1,6/0,8")
      (footprint "eagle-import:1,6_0,8")
      (libsource (lib "eagle-import") (part "1,6/0,8"))
    )
    (comp (ref "R7")
      (value "180")
      (footprint "eagle-import:0207_10")
      (libsource (lib "eagle-import") (part "R-US_0207/10"))
    )
    (comp (ref "R9")
      (value "120")
      (footprint "eagle-import:0207_10")
      (libsource (lib "eagle-import") (part "R-US_0207/10"))
    )
    (comp (ref "R16")
      (value "390")
      (footprint "eagle-import:0207_10")
      (libsource (lib "eagle-import") (part "R-US_0207/10"))
    )
    (comp (ref "R19")
      (value "10K")
      (footprint "eagle-import:0207_10")
      (libsource (lib "eagle-import") (part "R-US_0207/10"))
    )
  )
  (nets
    (net (code "1") (name "A-") (class "Default")
      (node (ref "E15") (pin "10") (pinfunction "PRE_10") (pintype "input"))
      (node (ref "E15") (pin "12") (pinfunction "D_12") (pintype "input"))
      (node (ref "E15") (pin "4") (pinfunction "PRE_4") (pintype "input"))
      (node (ref "E2") (pin "10") (pinfunction "PRE_10") (pintype "input"))
      (node (ref "E2") (pin "4") (pinfunction "PRE_4") (pintype "input"))
      (node (ref "E4") (pin "10") (pinfunction "ENT_10") (pintype "input"))
      (node (ref "E4") (pin "3") (pinfunction "A_3") (pintype "input"))
      (node (ref "E4") (pin "4") (pinfunction "B_4") (pintype "input"))
      (node (ref "E4") (pin "7") (pinfunction "ENP_7") (pintype "input"))
      (node (ref "E7") (pin "1") (pinfunction "CLR_1") (pintype "input"))
      (node (ref "R19") (pin "2") (pinfunction "2_2") (pintype "passive"))
    )
    (net (code "2") (name "AC00L") (class "Default")
      (node (ref "A04") (pin "B1") (pinfunction "P$2_B1") (pintype "bidirectional"))
      (node (ref "D04") (pin "B1") (pinfunction "P$2_B1") (pintype "bidirectional"))
      (node (ref "IC10") (pin "2") (pinfunction "O_2") (pintype "open_collector"))
    )
    (net (code "3") (name "AC01L") (class "Default")
      (node (ref "A04") (pin "D1") (pinfunction "P$2_D1") (pintype "bidirectional"))
      (node (ref "D04") (pin "D1") (pinfunction "P$2_D1") (pintype "bidirectional"))
      (node (ref "IC10") (pin "4") (pinfunction "O_4") (pintype "open_collector"))
    )
    (net (code "4") (name "AC02L") (class "Default")
      (node (ref "A04") (pin "E1") (pinfunction "P$2_E1") (pintype "bidirectional"))
      (node (ref "D04") (pin "E1") (pinfunction "P$2_E1") (pintype "bidirectional"))
      (node (ref "IC10") (pin "6") (pinfunction "O_6") (pintype "open_collector"))
    )
    (net (code "5") (name "AC03L") (class "Default")
      (node (ref "A04") (pin "H1") (pinfunction "P$2_H1") (pintype "bidirectional"))
      (node (ref "D04") (pin "H1") (pinfunction "P$2_H1") (pintype "bidirectional"))
      (node (ref "IC10") (pin "8") (pinfunction "O_8") (pintype "open_collector"))
    )
    (net (code "6") (name "AC04L") (class "Default")
      (node (ref "A04") (pin "J1") (pinfunction "P$2_J1") (pintype "bidirectional"))
      (node (ref "D04") (pin "J1") (pinfunction "P$2_J1") (pintype "bidirectional"))
      (node (ref "IC10") (pin "10") (pinfunction "O_10") (pintype "open_collector"))
    )
    (net (code "7") (name "AC05L") (class "Default")
      (node (ref "A04") (pin "L1") (pinfunction "P$2_L1") (pintype "bidirectional"))
      (node (ref "D04") (pin "L1") (pinfunction "P$2_L1") (pintype "bidirectional"))
      (node (ref "IC10") (pin "12") (pinfunction "O_12") (pintype "open_collector"))
    )
    (net (code "8") (name "AC06L") (class "Default")
      (node (ref "A04") (pin "M1") (pinfunction "P$2_M1") (pintype "bidirectional"))
      (node (ref "D04") (pin "M1") (pinfunction "P$2_M1") (pintype "bidirectional"))
      (node (ref "IC7") (pin "2") (pinfunction "O_2") (pintype "open_collector"))
    )
    (net (code "9") (name "AC07L") (class "Default")
      (node (ref "A04") (pin "P1") (pinfunction "P$2_P1") (pintype "bidirectional"))
      (node (ref "D04") (pin "P1") (pinfunction "P$2_P1") (pintype "bidirectional"))
      (node (ref "IC7") (pin "4") (pinfunction "O_4") (pintype "open_collector"))
    )
    (net (code "10") (name "AC08L") (class "Default")
      (node (ref "A04") (pin "S1") (pinfunction "P$2_S1") (pintype "bidirectional"))
      (node (ref "D04") (pin "S1") (pinfunction "P$2_S1") (pintype "bidirectional"))
      (node (ref "IC7") (pin "6") (pinfunction "O_6") (pintype "open_collector"))
    )
    (net (code "11") (name "AC09L") (class "Default")
      (node (ref "A04") (pin "D2") (pinfunction "P$2_D2") (pintype "bidirectional"))
      (node (ref "D04") (pin "D2") (pinfunction "P$2_D2") (pintype "bidirectional"))
      (node (ref "IC7") (pin "8") (pinfunction "O_8") (pintype "open_collector"))
    )
    (net (code "12") (name "AC10L") (class "Default")
      (node (ref "A04") (pin "E2") (pinfunction "P$2_E2") (pintype "bidirectional"))
      (node (ref "D04") (pin "E2") (pinfunction "P$2_E2") (pintype "bidirectional"))
      (node (ref "IC7") (pin "10") (pinfunction "O_10") (pintype "open_collector"))
    )
    (net (code "13") (name "AC11L") (class "Default")
      (node (ref "A04") (pin "H2") (pinfunction "P$2_H2") (pintype "bidirectional"))
      (node (ref "D04") (pin "H2") (pinfunction "P$2_H2") (pintype "bidirectional"))
      (node (ref "IC7") (pin "12") (pinfunction "O_12") (pintype "open_collector"))
    )
    (net (code "14") (name "B-") (class "Default")
      (node (ref "E21") (pin "10") (pinfunction "LD_10") (pintype "input"))
      (node (ref "E22") (pin "10") (pinfunction "PRE_10") (pintype "input"))
      (node (ref "E22") (pin "2") (pinfunction "D_2") (pintype "input"))
      (node (ref "E26") (pin "10") (pinfunction "PRE_10") (pintype "input"))
      (node (ref "E26") (pin "2") (pinfunction "D_2") (pintype "input"))
      (node (ref "E27") (pin "2") (pinfunction "PRE_2") (pintype "input"))
      (node (ref "E30") (pin "10") (pinfunction "PRE_10") (pintype "input"))
      (node (ref "E30") (pin "2") (pinfunction "D_2") (pintype "input"))
      (node (ref "E33") (pin "10") (pinfunction "LD_10") (pintype "input"))
      (node (ref "E9") (pin "10") (pinfunction "LD_10") (pintype "input"))
      (node (ref "R20") (pin "1") (pinfunction "1_1") (pintype "passive"))
    )
    (net (code "15") (name "BAC00") (class "Default")
      (node (ref "A02") (pin "B1") (pinfunction "P$2_B1") (pintype "bidirectional"))
      (node (ref "D02") (pin "B1") (pinfunction "P$2_B1") (pintype "bidirectional"))
      (node (ref "E42") (pin "1") (pinfunction "I0_1") (pintype "input"))
    )
    (net (code "16") (name "BAC01") (class "Default")
      (node (ref "A02") (pin "D1") (pinfunction "P$2_D1") (pintype "bidirectional"))
      (node (ref "D02") (pin "D1") (pinfunction "P$2_D1") (pintype "bidirectional"))
      (node (ref "E42") (pin "4") (pinfunction "I0_4") (pintype "input"))
    )
    (net (code "17") (name "BAC02") (class "Default")
      (node (ref "A02") (pin "E1") (pinfunction "P$2_E1") (pintype "bidirectional"))
      (node (ref "D02") (pin "E1") (pinfunction "P$2_E1") (pintype "bidirectional"))
      (node (ref "E42") (pin "9") (pinfunction "I0_9") (pintype "input"))
    )
    (net (code "18") (name "BAC03") (class "Default")
      (node (ref "A02") (pin "H1") (pinfunction "P$2_H1") (pintype "bidirectional"))
      (node (ref "D02") (pin "H1") (pinfunction "P$2_H1") (pintype "bidirectional"))
      (node (ref "E42") (pin "12") (pinfunction "I0_12") (pintype "input"))
    )
    (net (code "19") (name "BAC04") (class "Default")
      (node (ref "A02") (pin "J1") (pinfunction "P$2_J1") (pintype "bidirectional"))
      (node (ref "D02") (pin "J1") (pinfunction "P$2_J1") (pintype "bidirectional"))
      (node (ref "E43") (pin "1") (pinfunction "I0_1") (pintype "input"))
    )
    (net (code "20") (name "BAC05") (class "Default")
      (node (ref "A02") (pin "L1") (pinfunction "P$2_L1") (pintype "bidirectional"))
      (node (ref "D02") (pin "L1") (pinfunction "P$2_L1") (pintype "bidirectional"))
      (node (ref "E43") (pin "4") (pinfunction "I0_4") (pintype "input"))
    )
    (net (code "21") (name "BAC06") (class "Default")
      (node (ref "A02") (pin "M1") (pinfunction "P$2_M1") (pintype "bidirectional"))
      (node (ref "D02") (pin "M1") (pinfunction "P$2_M1") (pintype "bidirectional"))
      (node (ref "E43") (pin "9") (pinfunction "I0_9") (pintype "input"))
    )
    (net (code "22") (name "BAC07") (class "Default")
      (node (ref "A02") (pin "P1") (pinfunction "P$2_P1") (pintype "bidirectional"))
      (node (ref "D02") (pin "P1") (pinfunction "P$2_P1") (pintype "bidirectional"))
      (node (ref "E43") (pin "12") (pinfunction "I0_12") (pintype "input"))
    )
    (net (code "23") (name "BAC08") (class "Default")
      (node (ref "A02") (pin "S1") (pinfunction "P$2_S1") (pintype "bidirectional"))
      (node (ref "D02") (pin "S1") (pinfunction "P$2_S1") (pintype "bidirectional"))
      (node (ref "E44") (pin "1") (pinfunction "I0_1") (pintype "input"))
    )
    (net (code "24") (name "BAC09") (class "Default")
      (node (ref "A02") (pin "D2") (pinfunction "P$2_D2") (pintype "bidirectional"))
      (node (ref "D02") (pin "D2") (pinfunction "P$2_D2") (pintype "bidirectional"))
      (node (ref "E44") (pin "4") (pinfunction "I0_4") (pintype "input"))
    )
    (net (code "25") (name "BAC10") (class "Default")
      (node (ref "A02") (pin "E2") (pinfunction "P$2_E2") (pintype "bidirectional"))
      (node (ref "D02") (pin "E2") (pinfunction "P$2_E2") (pintype "bidirectional"))
      (node (ref "E44") (pin "9") (pinfunction "I0_9") (pintype "input"))
    )
    (net (code "26") (name "BAC11") (class "Default")
      (node (ref "A02") (pin "H2") (pinfunction "P$2_H2") (pintype "bidirectional"))
      (node (ref "D02") (pin "H2") (pinfunction "P$2_H2") (pintype "bidirectional"))
      (node (ref "E44") (pin "12") (pinfunction "I0_12") (pintype "input"))
    )
    (net (code "27") (name "BACLR") (class "Default")
      (node (ref "A04") (pin "P2") (pinfunction "P$2_P2") (pintype "bidirectional"))
      (node (ref "D04") (pin "P2") (pinfunction "P$2_P2") (pintype "bidirectional"))
      (node (ref "IC4") (pin "8") (pinfunction "O_8") (pintype "output"))
    )
    (net (code "28") (name "BIOP1") (class "Default")
      (node (ref "A02") (pin "K2") (pinfunction "P$2_K2") (pintype "bidirectional"))
      (node (ref "D02") (pin "K2") (pinfunction "P$2_K2") (pintype "bidirectional"))
      (node (ref "IC9") (pin "1") (pinfunction "I0_1") (pintype "input"))
    )
    (net (code "29") (name "BIOP2") (class "Default")
      (node (ref "A02") (pin "M2") (pinfunction "P$2_M2") (pintype "bidirectional"))
      (node (ref "D02") (pin "M2") (pinfunction "P$2_M2") (pintype "bidirectional"))
      (node (ref "IC9") (pin "2") (pinfunction "I1_2") (pintype "input"))
    )
    (net (code "30") (name "BIOP4") (class "Default")
      (node (ref "A02") (pin "P2") (pinfunction "P$2_P2") (pintype "bidirectional"))
      (node (ref "D02") (pin "P2") (pinfunction "P$2_P2") (pintype "bidirectional"))
      (node (ref "IC9") (pin "13") (pinfunction "I2_13") (pintype "input"))
    )
    (net (code "31") (name "BIRQ") (class "Default")
      (node (ref "A04") (pin "M2") (pinfunction "P$2_M2") (pintype "bidirectional"))
      (node (ref "D04") (pin "M2") (pinfunction "P$2_M2") (pintype "bidirectional"))
      (node (ref "IC2") (pin "4") (pinfunction "O_4") (pintype "open_collector"))
    )
    (net (code "32") (name "BMB00") (class "Default")
      (node (ref "A03") (pin "B1") (pinfunction "P$2_B1") (pintype "bidirectional"))
      (node (ref "D03") (pin "B1") (pinfunction "P$2_B1") (pintype "bidirectional"))
      (node (ref "IC4") (pin "12") (pinfunction "I0_12") (pintype "input"))
    )
    (net (code "33") (name "BMB01") (class "Default")
      (node (ref "A03") (pin "D1") (pinfunction "P$2_D1") (pintype "bidirectional"))
      (node (ref "D03") (pin "D1") (pinfunction "P$2_D1") (pintype "bidirectional"))
      (node (ref "IC4") (pin "13") (pinfunction "I1_13") (pintype "input"))
    )
    (net (code "34") (name "BMB02") (class "Default")
      (node (ref "A03") (pin "E1") (pinfunction "P$2_E1") (pintype "bidirectional"))
      (node (ref "D03") (pin "E1") (pinfunction "P$2_E1") (pintype "bidirectional"))
      (node (ref "IC4") (pin "2") (pinfunction "I1_2") (pintype "input"))
    )
    (net (code "35") (name "BMB03") (class "Default")
      (node (ref "A03") (pin "J1") (pinfunction "P$2_J1") (pintype "bidirectional"))
      (node (ref "D03") (pin "J1") (pinfunction "P$2_J1") (pintype "bidirectional"))
    )
    (net (code "36") (name "BMB04") (class "Default")
      (node (ref "A03") (pin "M1") (pinfunction "P$2_M1") (pintype "bidirectional"))
      (node (ref "D03") (pin "M1") (pinfunction "P$2_M1") (pintype "bidirectional"))
    )
    (net (code "37") (name "BMB05") (class "Default")
      (node (ref "A03") (pin "S1") (pinfunction "P$2_S1") (pintype "bidirectional"))
      (node (ref "D03") (pin "S1") (pinfunction "P$2_S1") (pintype "bidirectional"))
    )
    (net (code "38") (name "BMB06") (class "Default")
      (node (ref "A03") (pin "E2") (pinfunction "P$2_E2") (pintype "bidirectional"))
      (node (ref "D03") (pin "E2") (pinfunction "P$2_E2") (pintype "bidirectional"))
    )
    (net (code "39") (name "BMB07") (class "Default")
      (node (ref "A03") (pin "K2") (pinfunction "P$2_K2") (pintype "bidirectional"))
      (node (ref "D03") (pin "K2") (pinfunction "P$2_K2") (pintype "bidirectional"))
    )
    (net (code "40") (name "BMB08") (class "Default")
      (node (ref "A03") (pin "P2") (pinfunction "P$2_P2") (pintype "bidirectional"))
      (node (ref "D03") (pin "P2") (pinfunction "P$2_P2") (pintype "bidirectional"))
    )
    (net (code "41") (name "BMB09") (class "Default")
      (node (ref "A03") (pin "S2") (pinfunction "P$2_S2") (pintype "bidirectional"))
      (node (ref "D03") (pin "S2") (pinfunction "P$2_S2") (pintype "bidirectional"))
      (node (ref "IC1") (pin "1") (pinfunction "I_1") (pintype "input"))
    )
    (net (code "42") (name "BMB10") (class "Default")
      (node (ref "A03") (pin "T2") (pinfunction "P$2_T2") (pintype "bidirectional"))
      (node (ref "D03") (pin "T2") (pinfunction "P$2_T2") (pintype "bidirectional"))
      (node (ref "IC1") (pin "3") (pinfunction "I_3") (pintype "input"))
    )
    (net (code "43") (name "BMB11") (class "Default")
      (node (ref "A03") (pin "V2") (pinfunction "P$2_V2") (pintype "bidirectional"))
      (node (ref "D03") (pin "V2") (pinfunction "P$2_V2") (pintype "bidirectional"))
      (node (ref "IC1") (pin "5") (pinfunction "I_5") (pintype "input"))
    )
    (net (code "44") (name "BRD_L") (class "Default")
      (node (ref "IC1") (pin "8") (pinfunction "O_8") (pintype "output"))
      (node (ref "IC5") (pin "12") (pinfunction "I1_12") (pintype "input"))
      (node (ref "IC5") (pin "2") (pinfunction "I0_2") (pintype "input"))
      (node (ref "IC5") (pin "6") (pinfunction "I1_6") (pintype "input"))
      (node (ref "IC5") (pin "8") (pinfunction "I0_8") (pintype "input"))
      (node (ref "IC6") (pin "12") (pinfunction "I1_12") (pintype "input"))
      (node (ref "IC6") (pin "2") (pinfunction "I0_2") (pintype "input"))
      (node (ref "IC6") (pin "6") (pinfunction "I1_6") (pintype "input"))
      (node (ref "IC6") (pin "9") (pinfunction "I1_9") (pintype "input"))
      (node (ref "IC8") (pin "12") (pinfunction "I1_12") (pintype "input"))
      (node (ref "IC8") (pin "3") (pinfunction "I1_3") (pintype "input"))
      (node (ref "IC8") (pin "6") (pinfunction "I1_6") (pintype "input"))
      (node (ref "IC8") (pin "9") (pinfunction "I1_9") (pintype "input"))
    )
    (net (code "45") (name "BRUN") (class "Default")
      (node (ref "A04") (pin "S2") (pinfunction "P$2_S2") (pintype "bidirectional"))
      (node (ref "D04") (pin "S2") (pinfunction "P$2_S2") (pintype "bidirectional"))
    )
    (net (code "46") (name "BSKIP") (class "Default")
      (node (ref "A04") (pin "K2") (pinfunction "P$2_K2") (pintype "bidirectional"))
      (node (ref "D04") (pin "K2") (pinfunction "P$2_K2") (pintype "bidirectional"))
      (node (ref "IC2") (pin "2") (pinfunction "O_2") (pintype "open_collector"))
    )
    (net (code "47") (name "BTP3") (class "Default")
      (node (ref "E28") (pin "13") (pinfunction "I3_13") (pintype "input"))
      (node (ref "E28") (pin "2") (pinfunction "I1_2") (pintype "input"))
      (node (ref "E32") (pin "12") (pinfunction "O_12") (pintype "output"))
      (node (ref "E7") (pin "3") (pinfunction "CLK_3") (pintype "input"))
    )
    (net (code "48") (name "BTP4") (class "Default")
      (node (ref "E22") (pin "11") (pinfunction "CLK_11") (pintype "input"))
      (node (ref "E26") (pin "11") (pinfunction "CLK_11") (pintype "input"))
      (node (ref "E30") (pin "11") (pinfunction "CLK_11") (pintype "input"))
      (node (ref "E8") (pin "8") (pinfunction "O_8") (pintype "output"))
    )
    (net (code "49") (name "BTS3") (class "Default")
      (node (ref "A02") (pin "S2") (pinfunction "P$2_S2") (pintype "bidirectional"))
      (node (ref "D02") (pin "S2") (pinfunction "P$2_S2") (pintype "bidirectional"))
      (node (ref "IC1") (pin "11") (pinfunction "I_11") (pintype "input"))
    )
    (net (code "50") (name "BWR") (class "Default")
      (node (ref "E42") (pin "10") (pinfunction "I1_10") (pintype "input"))
      (node (ref "E42") (pin "13") (pinfunction "I1_13") (pintype "input"))
      (node (ref "E42") (pin "2") (pinfunction "I1_2") (pintype "input"))
      (node (ref "E42") (pin "5") (pinfunction "I1_5") (pintype "input"))
      (node (ref "E43") (pin "10") (pinfunction "I1_10") (pintype "input"))
      (node (ref "E43") (pin "13") (pinfunction "I1_13") (pintype "input"))
      (node (ref "E43") (pin "2") (pinfunction "I1_2") (pintype "input"))
      (node (ref "E43") (pin "5") (pinfunction "I1_5") (pintype "input"))
      (node (ref "E44") (pin "10") (pinfunction "I1_10") (pintype "input"))
      (node (ref "E44") (pin "13") (pinfunction "I1_13") (pintype "input"))
      (node (ref "E44") (pin "2") (pinfunction "I1_2") (pintype "input"))
      (node (ref "E44") (pin "5") (pinfunction "I1_5") (pintype "input"))
      (node (ref "IC19") (pin "8") (pinfunction "O_8") (pintype "output"))
    )
    (net (code "51") (name "B_MAINT") (class "Default")
      (node (ref "E32") (pin "10") (pinfunction "O_10") (pintype "output"))
      (node (ref "E36") (pin "7") (pinfunction "FORCE0_7") (pintype "input"))
      (node (ref "E36") (pin "9") (pinfunction "FORCE0_9") (pintype "input"))
    )
    (net (code "52") (name "DATA0") (class "Default")
      (node (ref "E1") (pin "14") (pinfunction "A3_14") (pintype "output"))
      (node (ref "E9") (pin "14") (pinfunction "D_14") (pintype "input"))
    )
    (net (code "53") (name "DATA1") (class "Default")
      (node (ref "E1") (pin "12") (pinfunction "A2_12") (pintype "output"))
      (node (ref "E9") (pin "15") (pinfunction "C_15") (pintype "input"))
    )
    (net (code "54") (name "DATA2") (class "Default")
      (node (ref "E1") (pin "10") (pinfunction "A1_10") (pintype "output"))
      (node (ref "E9") (pin "2") (pinfunction "B_2") (pintype "input"))
    )
    (net (code "55") (name "DATA3") (class "Default")
      (node (ref "E1") (pin "6") (pinfunction "A3_6") (pintype "output"))
      (node (ref "E9") (pin "3") (pinfunction "A_3") (pintype "input"))
    )
    (net (code "56") (name "DATA4") (class "Default")
      (node (ref "E1") (pin "4") (pinfunction "A2_4") (pintype "output"))
      (node (ref "E2") (pin "12") (pinfunction "D_12") (pintype "input"))
      (node (ref "E21") (pin "14") (pinfunction "D_14") (pintype "input"))
    )
    (net (code "57") (name "DATA5") (class "Default")
      (node (ref "E1") (pin "2") (pinfunction "A1_2") (pintype "output"))
      (node (ref "E12") (pin "9") (pinfunction "I0_9") (pintype "input"))
      (node (ref "E2") (pin "2") (pinfunction "D_2") (pintype "input"))
      (node (ref "E21") (pin "15") (pinfunction "C_15") (pintype "input"))
    )
    (net (code "58") (name "DATA6") (class "Default")
      (node (ref "E21") (pin "2") (pinfunction "B_2") (pintype "input"))
      (node (ref "E25") (pin "14") (pinfunction "A3_14") (pintype "output"))
    )
    (net (code "59") (name "DATA7") (class "Default")
      (node (ref "E21") (pin "3") (pinfunction "A_3") (pintype "input"))
      (node (ref "E25") (pin "12") (pinfunction "A2_12") (pintype "output"))
    )
    (net (code "60") (name "DATA8") (class "Default")
      (node (ref "E25") (pin "10") (pinfunction "A1_10") (pintype "output"))
      (node (ref "E33") (pin "14") (pinfunction "D_14") (pintype "input"))
    )
    (net (code "61") (name "DATA9") (class "Default")
      (node (ref "E25") (pin "6") (pinfunction "A3_6") (pintype "output"))
      (node (ref "E33") (pin "15") (pinfunction "C_15") (pintype "input"))
    )
    (net (code "62") (name "DATA10") (class "Default")
      (node (ref "E25") (pin "4") (pinfunction "A2_4") (pintype "output"))
      (node (ref "E33") (pin "2") (pinfunction "B_2") (pintype "input"))
    )
    (net (code "63") (name "DATA11") (class "Default")
      (node (ref "E15") (pin "2") (pinfunction "D_2") (pintype "input"))
      (node (ref "E25") (pin "2") (pinfunction "A1_2") (pintype "output"))
      (node (ref "E33") (pin "3") (pinfunction "A_3") (pintype "input"))
    )
    (net (code "64") (name "DONE") (class "Default")
      (node (ref "E20") (pin "11") (pinfunction "I2_11") (pintype "input"))
      (node (ref "E22") (pin "3") (pinfunction "CLK_3") (pintype "input"))
      (node (ref "E28") (pin "5") (pinfunction "I3_5") (pintype "input"))
      (node (ref "E32") (pin "9") (pinfunction "I_9") (pintype "input"))
      (node (ref "E36") (pin "6") (pinfunction "A3_6") (pintype "output"))
      (node (ref "E39") (pin "11") (pinfunction "I0_11") (pintype "input"))
    )
    (net (code "65") (name "EIGHT") (class "Default")
      (node (ref "E12") (pin "13") (pinfunction "I1_13") (pintype "input"))
      (node (ref "E2") (pin "5") (pinfunction "Q_5") (pintype "output"))
      (node (ref "E3") (pin "4") (pinfunction "I1_4") (pintype "input"))
    )
    (net (code "66") (name "ERROR") (class "Default")
      (node (ref "E26") (pin "3") (pinfunction "CLK_3") (pintype "input"))
      (node (ref "E36") (pin "2") (pinfunction "A1_2") (pintype "output"))
    )
    (net (code "67") (name "GND") (class "Default")
      (node (ref "C1") (pin "2") (pinfunction "2_2") (pintype "passive"))
      (node (ref "C10") (pin "2") (pinfunction "2_2") (pintype "passive"))
      (node (ref "C11") (pin "2") (pinfunction "2_2") (pintype "passive"))
      (node (ref "C12") (pin "2") (pinfunction "2_2") (pintype "passive"))
      (node (ref "C13") (pin "2") (pinfunction "2_2") (pintype "passive"))
      (node (ref "C14") (pin "2") (pinfunction "2_2") (pintype "passive"))
      (node (ref "C15") (pin "2") (pinfunction "2_2") (pintype "passive"))
      (node (ref "C16") (pin "2") (pinfunction "2_2") (pintype "passive"))
      (node (ref "C17") (pin "2") (pinfunction "2_2") (pintype "passive"))
      (node (ref "C18") (pin "2") (pinfunction "2_2") (pintype "passive"))
      (node (ref "C19") (pin "2") (pinfunction "2_2") (pintype "passive"))
      (node (ref "C2") (pin "2") (pinfunction "2_2") (pintype "passive"))
      (node (ref "C20") (pin "2") (pinfunction "2_2") (pintype "passive"))
      (node (ref "C21") (pin "2") (pinfunction "2_2") (pintype "passive"))
      (node (ref "C22") (pin "2") (pinfunction "2_2") (pintype "passive"))
      (node (ref "C23") (pin "2") (pinfunction "2_2") (pintype "passive"))
      (node (ref "C24") (pin "2") (pinfunction "2_2") (pintype "passive"))
      (node (ref "C25") (pin "2") (pinfunction "2_2") (pintype "passive"))
      (node (ref "C26") (pin "2") (pinfunction "2_2") (pintype "passive"))
      (node (ref "C27A") (pin "2") (pinfunction "2_2") (pintype "passive"))
      (node (ref "C28") (pin "2") (pinfunction "2_2") (pintype "passive"))
      (node (ref "C29") (pin "2") (pinfunction "2_2") (pintype "passive"))
      (node (ref "C3") (pin "2") (pinfunction "2_2") (pintype "passive"))
      (node (ref "C30") (pin "2") (pinfunction "2_2") (pintype "passive"))
      (node (ref "C31") (pin "2") (pinfunction "2_2") (pintype "passive"))
      (node (ref "C32") (pin "2") (pinfunction "2_2") (pintype "passive"))
      (node (ref "C33") (pin "2") (pinfunction "2_2") (pintype "passive"))
      (node (ref "C34") (pin "2") (pinfunction "2_2") (pintype "passive"))
      (node (ref "C35") (pin "2") (pinfunction "2_2") (pintype "passive"))
      (node (ref "C36") (pin "2") (pinfunction "2_2") (pintype "passive"))
      (node (ref "C37") (pin "2") (pinfunction "2_2") (pintype "passive"))
      (node (ref "C38") (pin "2") (pinfunction "2_2") (pintype "passive"))
      (node (ref "C39") (pin "2") (pinfunction "2_2") (pintype "passive"))
      (node (ref "C4") (pin "2") (pinfunction "2_2") (pintype "passive"))
      (node (ref "C40") (pin "2") (pinfunction "2_2") (pintype "passive"))
      (node (ref "C41") (pin "2") (pinfunction "2_2") (pintype "passive"))
      (node (ref "C42") (pin "-") (pinfunction "-_-") (pintype "passive"))
      (node (ref "C43") (pin "-") (pinfunction "-_-") (pintype "passive"))
      (node (ref "C44") (pin "-") (pinfunction "-_-") (pintype "passive"))
      (node (ref "C45") (pin "-") (pinfunction "-_-") (pintype "passive"))
      (node (ref "C5") (pin "2") (pinfunction "2_2") (pintype "passive"))
      (node (ref "C6") (pin "2") (pinfunction "2_2") (pintype "passive"))
      (node (ref "C7") (pin "2") (pinfunction "2_2") (pintype "passive"))
      (node (ref "C8") (pin "2") (pinfunction "2_2") (pintype "passive"))
      (node (ref "C9") (pin "2") (pinfunction "2_2") (pintype "passive"))
      (node (ref "DRIVE") (pin "A") (pinfunction "1_A") (pintype "bidirectional"))
      (node (ref "DRIVE") (pin "AA") (pinfunction "23_AA") (pintype "bidirectional"))
      (node (ref "DRIVE") (pin "B") (pinfunction "2_B") (pintype "bidirectional"))
      (node (ref "DRIVE") (pin "C") (pinfunction "3_C") (pintype "bidirectional"))
      (node (ref "DRIVE") (pin "CC") (pinfunction "25_CC") (pintype "bidirectional"))
      (node (ref "DRIVE") (pin "DD") (pinfunction "26_DD") (pintype "bidirectional"))
      (node (ref "DRIVE") (pin "E") (pinfunction "5_E") (pintype "bidirectional"))
      (node (ref "DRIVE") (pin "EE") (pinfunction "27_EE") (pintype "bidirectional"))
      (node (ref "DRIVE") (pin "F") (pinfunction "6_F") (pintype "bidirectional"))
      (node (ref "DRIVE") (pin "H") (pinfunction "7_H") (pintype "bidirectional"))
      (node (ref "DRIVE") (pin "HH") (pinfunction "29_HH") (pintype "bidirectional"))
      (node (ref "DRIVE") (pin "JJ") (pinfunction "30_JJ") (pintype "bidirectional"))
      (node (ref "DRIVE") (pin "K") (pinfunction "9_K") (pintype "bidirectional"))
      (node (ref "DRIVE") (pin "KK") (pinfunction "31_KK") (pintype "bidirectional"))
      (node (ref "DRIVE") (pin "L") (pinfunction "10_L") (pintype "bidirectional"))
      (node (ref "DRIVE") (pin "M") (pinfunction "11_M") (pintype "bidirectional"))
      (node (ref "DRIVE") (pin "MM") (pinfunction "33_MM") (pintype "bidirectional"))
      (node (ref "DRIVE") (pin "NN") (pinfunction "34_NN") (pintype "bidirectional"))
      (node (ref "DRIVE") (pin "P") (pinfunction "13_P") (pintype "bidirectional"))
      (node (ref "DRIVE") (pin "PP") (pinfunction "35_PP") (pintype "bidirectional"))
      (node (ref "DRIVE") (pin "R") (pinfunction "14_R") (pintype "bidirectional"))
      (node (ref "DRIVE") (pin "S") (pinfunction "15_S") (pintype "bidirectional"))
      (node (ref "DRIVE") (pin "SS") (pinfunction "37_SS") (pintype "bidirectional"))
      (node (ref "DRIVE") (pin "TT") (pinfunction "38_TT") (pintype "bidirectional"))
      (node (ref "DRIVE") (pin "U") (pinfunction "17_U") (pintype "bidirectional"))
      (node (ref "DRIVE") (pin "UU") (pinfunction "39_UU") (pintype "bidirectional"))
      (node (ref "DRIVE") (pin "V") (pinfunction "18_V") (pintype "bidirectional"))
      (node (ref "DRIVE") (pin "VV") (pinfunction "40_VV") (pintype "bidirectional"))
      (node (ref "DRIVE") (pin "W") (pinfunction "19_W") (pintype "bidirectional"))
      (node (ref "DRIVE") (pin "Y") (pinfunction "21_Y") (pintype "bidirectional"))
      (node (ref "DRIVE") (pin "Z") (pinfunction "22_Z") (pintype "bidirectional"))
      (node (ref "E11") (pin "10") (pinfunction "I1_10") (pintype "input"))
      (node (ref "E11") (pin "5") (pinfunction "I1_5") (pintype "input"))
      (node (ref "E11") (pin "7") (pinfunction "I1_7") (pintype "input"))
      (node (ref "E39") (pin "7") (pinfunction "I1_7") (pintype "input"))
      (node (ref "E4") (pin "6") (pinfunction "D_6") (pintype "input"))
      (node (ref "R10") (pin "1") (pinfunction "1_1") (pintype "passive"))
      (node (ref "R11") (pin "1") (pinfunction "1_1") (pintype "passive"))
      (node (ref "R12") (pin "1") (pinfunction "1_1") (pintype "passive"))
      (node (ref "R13") (pin "1") (pinfunction "1_1") (pintype "passive"))
      (node (ref "R14") (pin "1") (pinfunction "1_1") (pintype "passive"))
      (node (ref "R15") (pin "1") (pinfunction "1_1") (pintype "passive"))
      (node (ref "R16") (pin "1") (pinfunction "1_1") (pintype "passive"))
      (node (ref "R17") (pin "1") (pinfunction "1_1") (pintype "passive"))
      (node (ref "U$2") (pin "AC2") (pinfunction "1_AC2") (pintype "bidirectional"))
      (node (ref "U$2") (pin "AT1") (pinfunction "1_AT1") (pintype "bidirectional"))
      (node (ref "U$2") (pin "AT2") (pinfunction "1_AT2") (pintype "bidirectional"))
      (node (ref "U$2") (pin "BC2") (pinfunction "1_BC2") (pintype "bidirectional"))
      (node (ref "U$2") (pin "BT1") (pinfunction "1_BT1") (pintype "bidirectional"))
      (node (ref "U$2") (pin "CC2") (pinfunction "1_CC2") (pintype "bidirectional"))
      (node (ref "U$2") (pin "CT1") (pinfunction "1_CT1") (pintype "bidirectional"))
      (node (ref "U$2") (pin "DC2") (pinfunction "1_DC2") (pintype "bidirectional"))
      (node (ref "U$2") (pin "DT1") (pinfunction "1_DT1") (pintype "bidirectional"))
    )
    (net (code "68") (name "INIT") (class "Default")
      (node (ref "E19") (pin "6") (pinfunction "I1_6") (pintype "input"))
      (node (ref "E23") (pin "3") (pinfunction "I1_3") (pintype "input"))
      (node (ref "E23") (pin "6") (pinfunction "I1_6") (pintype "input"))
      (node (ref "E24") (pin "3") (pinfunction "O_3") (pintype "output"))
      (node (ref "E32") (pin "3") (pinfunction "I_3") (pintype "input"))
      (node (ref "E37") (pin "11") (pinfunction "I0_11") (pintype "input"))
      (node (ref "E37") (pin "12") (pinfunction "I1_12") (pintype "input"))
      (node (ref "E6") (pin "12") (pinfunction "I1_12") (pintype "input"))
      (node (ref "E8") (pin "5") (pinfunction "I_5") (pintype "input"))
    )
    (net (code "69") (name "INITIALIZE") (class "Default")
      (node (ref "A02") (pin "V2") (pinfunction "P$2_V2") (pintype "bidirectional"))
      (node (ref "C27") (pin "R1") (pinfunction "P$2_R1") (pintype "bidirectional"))
      (node (ref "D02") (pin "V2") (pinfunction "P$2_V2") (pintype "bidirectional"))
      (node (ref "E11") (pin "6") (pinfunction "I0_6") (pintype "input"))
      (node (ref "U$2") (pin "CR1") (pinfunction "1_CR1") (pintype "bidirectional"))
    )
    (net (code "70") (name "IOT") (class "Default")
      (node (ref "IC3") (pin "2") (pinfunction "D_2") (pintype "input"))
      (node (ref "IC4") (pin "3") (pinfunction "O_3") (pintype "output"))
    )
    (net (code "71") (name "LCD_IOT") (class "Default")
      (node (ref "E12") (pin "10") (pinfunction "I1_10") (pintype "input"))
      (node (ref "E28") (pin "4") (pinfunction "I2_4") (pintype "input"))
      (node (ref "E38") (pin "4") (pinfunction "O_4") (pintype "output"))
    )
    (net (code "72") (name "MAINT") (class "Default")
      (node (ref "E2") (pin "9") (pinfunction "Q_9") (pintype "output"))
      (node (ref "E20") (pin "9") (pinfunction "I0_9") (pintype "input"))
    )
    (net (code "73") (name "MSB8") (class "Default")
      (node (ref "E17") (pin "3") (pinfunction "I1_3") (pintype "input"))
      (node (ref "E21") (pin "11") (pinfunction "QD_11") (pintype "output"))
      (node (ref "E3") (pin "5") (pinfunction "I2_5") (pintype "input"))
      (node (ref "E9") (pin "4") (pinfunction "SER_4") (pintype "input"))
    )
    (net (code "74") (name "MSB12") (class "Default")
      (node (ref "E3") (pin "2") (pinfunction "I1_2") (pintype "input"))
      (node (ref "E5") (pin "3") (pinfunction "I1_3") (pintype "input"))
      (node (ref "E9") (pin "11") (pinfunction "QD_11") (pintype "output"))
    )
    (net (code "75") (name "Net-(E2A-CLK)") (class "Default")
      (node (ref "E2") (pin "11") (pinfunction "CLK_11") (pintype "input"))
      (node (ref "E2") (pin "3") (pinfunction "CLK_3") (pintype "input"))
      (node (ref "E6") (pin "1") (pinfunction "O_1") (pintype "output"))
    )
    (net (code "76") (name "Net-(E3A-I2)") (class "Default")
      (node (ref "E3") (pin "13") (pinfunction "I2_13") (pintype "input"))
      (node (ref "E3") (pin "3") (pinfunction "I0_3") (pintype "input"))
      (node (ref "E8") (pin "2") (pinfunction "O_2") (pintype "output"))
    )
    (net (code "77") (name "Net-(E3A-O)") (class "Default")
      (node (ref "E3") (pin "11") (pinfunction "I2_11") (pintype "input"))
      (node (ref "E3") (pin "12") (pinfunction "O_12") (pintype "output"))
    )
    (net (code "78") (name "Net-(E3B-O)") (class "Default")
      (node (ref "E3") (pin "6") (pinfunction "O_6") (pintype "output"))
      (node (ref "E3") (pin "9") (pinfunction "I0_9") (pintype "input"))
    )
    (net (code "79") (name "Net-(E4A-CLK)") (class "Default")
      (node (ref "E4") (pin "2") (pinfunction "CLK_2") (pintype "input"))
      (node (ref "E8") (pin "13") (pinfunction "I_13") (pintype "input"))
      (node (ref "E8") (pin "4") (pinfunction "O_4") (pintype "output"))
    )
    (net (code "80") (name "Net-(E5B-I1)") (class "Default")
      (node (ref "E5") (pin "6") (pinfunction "I1_6") (pintype "input"))
      (node (ref "E9") (pin "9") (pinfunction "QC_9") (pintype "output"))
    )
    (net (code "81") (name "Net-(E5C-I1)") (class "Default")
      (node (ref "E5") (pin "9") (pinfunction "I1_9") (pintype "input"))
      (node (ref "E9") (pin "7") (pinfunction "QB_7") (pintype "output"))
    )
    (net (code "82") (name "Net-(E5D-I1)") (class "Default")
      (node (ref "E5") (pin "12") (pinfunction "I1_12") (pintype "input"))
      (node (ref "E9") (pin "5") (pinfunction "QA_5") (pintype "output"))
    )
    (net (code "83") (name "Net-(E10A-I1)") (class "Default")
      (node (ref "E10") (pin "2") (pinfunction "I1_2") (pintype "input"))
      (node (ref "E10") (pin "6") (pinfunction "O_6") (pintype "output"))
      (node (ref "E14") (pin "12") (pinfunction "I1_12") (pintype "input"))
    )
    (net (code "84") (name "Net-(E10A-O)") (class "Default")
      (node (ref "E10") (pin "12") (pinfunction "O_12") (pintype "output"))
      (node (ref "E12") (pin "5") (pinfunction "I1_5") (pintype "input"))
    )
    (net (code "85") (name "Net-(E10C-O)") (class "Default")
      (node (ref "E10") (pin "8") (pinfunction "O_8") (pintype "output"))
      (node (ref "E18") (pin "8") (pinfunction "I0_8") (pintype "input"))
      (node (ref "E18") (pin "9") (pinfunction "I1_9") (pintype "input"))
    )
    (net (code "86") (name "Net-(E11A-O)") (class "Default")
      (node (ref "E11") (pin "3") (pinfunction "O_3") (pintype "output"))
      (node (ref "E7") (pin "4") (pinfunction "PRE_4") (pintype "input"))
      (node (ref "E8") (pin "9") (pinfunction "I_9") (pintype "input"))
    )
    (net (code "87") (name "Net-(E11B-O)") (class "Default")
      (node (ref "E11") (pin "2") (pinfunction "O_2") (pintype "output"))
      (node (ref "E24") (pin "1") (pinfunction "I0_1") (pintype "input"))
    )
    (net (code "88") (name "Net-(E12A-I0)") (class "Default")
      (node (ref "E12") (pin "1") (pinfunction "I0_1") (pintype "input"))
      (node (ref "E12") (pin "11") (pinfunction "O_11") (pintype "output"))
    )
    (net (code "89") (name "Net-(E12A-I1)") (class "Default")
      (node (ref "E12") (pin "2") (pinfunction "I1_2") (pintype "input"))
      (node (ref "E12") (pin "8") (pinfunction "O_8") (pintype "output"))
    )
    (net (code "90") (name "Net-(E12A-O)") (class "Default")
      (node (ref "E12") (pin "3") (pinfunction "O_3") (pintype "output"))
      (node (ref "E4") (pin "5") (pinfunction "C_5") (pintype "input"))
    )
    (net (code "91") (name "Net-(E12B-O)") (class "Default")
      (node (ref "E12") (pin "6") (pinfunction "O_6") (pintype "output"))
      (node (ref "E14") (pin "2") (pinfunction "I0_2") (pintype "input"))
      (node (ref "E14") (pin "3") (pinfunction "I1_3") (pintype "input"))
    )
    (net (code "92") (name "Net-(E14B-I1)") (class "Default")
      (node (ref "E14") (pin "6") (pinfunction "I1_6") (pintype "input"))
      (node (ref "E27") (pin "16") (pinfunction "K_16") (pintype "input"))
      (node (ref "E27") (pin "4") (pinfunction "J_4") (pintype "input"))
      (node (ref "E3") (pin "8") (pinfunction "O_8") (pintype "output"))
    )
    (net (code "93") (name "Net-(E15A-CLK)") (class "Default")
      (node (ref "E15") (pin "3") (pinfunction "CLK_3") (pintype "input"))
      (node (ref "E6") (pin "4") (pinfunction "O_4") (pintype "output"))
    )
    (net (code "94") (name "Net-(E15A-Q)") (class "Default")
      (node (ref "E15") (pin "5") (pinfunction "Q_5") (pintype "output"))
      (node (ref "E18") (pin "5") (pinfunction "I0_5") (pintype "input"))
    )
    (net (code "95") (name "Net-(E15B-CLK)") (class "Default")
      (node (ref "E15") (pin "11") (pinfunction "CLK_11") (pintype "input"))
      (node (ref "E24") (pin "6") (pinfunction "O_6") (pintype "output"))
    )
    (net (code "96") (name "Net-(E15B-CLR)") (class "Default")
      (node (ref "E15") (pin "13") (pinfunction "CLR_13") (pintype "input"))
      (node (ref "E16") (pin "8") (pinfunction "O_8") (pintype "output"))
    )
    (net (code "97") (name "Net-(E16A-I1)") (class "Default")
      (node (ref "E16") (pin "2") (pinfunction "I1_2") (pintype "input"))
      (node (ref "E17") (pin "11") (pinfunction "I0_11") (pintype "input"))
      (node (ref "E17") (pin "2") (pinfunction "I0_2") (pintype "input"))
      (node (ref "E17") (pin "5") (pinfunction "I0_5") (pintype "input"))
      (node (ref "E17") (pin "8") (pinfunction "I0_8") (pintype "input"))
      (node (ref "E19") (pin "13") (pinfunction "O_13") (pintype "output"))
      (node (ref "E29") (pin "11") (pinfunction "I0_11") (pintype "input"))
      (node (ref "E29") (pin "2") (pinfunction "I0_2") (pintype "input"))
      (node (ref "E29") (pin "5") (pinfunction "I0_5") (pintype "input"))
      (node (ref "E29") (pin "8") (pinfunction "I0_8") (pintype "input"))
    )
    (net (code "98") (name "Net-(E16A-O)") (class "Default")
      (node (ref "E16") (pin "3") (pinfunction "O_3") (pintype "output"))
      (node (ref "E5") (pin "11") (pinfunction "I0_11") (pintype "input"))
      (node (ref "E5") (pin "2") (pinfunction "I0_2") (pintype "input"))
      (node (ref "E5") (pin "5") (pinfunction "I0_5") (pintype "input"))
      (node (ref "E5") (pin "8") (pinfunction "I0_8") (pintype "input"))
    )
    (net (code "99") (name "Net-(E16B-O)") (class "Default")
      (node (ref "E16") (pin "6") (pinfunction "O_6") (pintype "output"))
      (node (ref "E20") (pin "2") (pinfunction "I1_2") (pintype "input"))
    )
    (net (code "100") (name "Net-(E16C-I0)") (class "Default")
      (node (ref "E16") (pin "9") (pinfunction "I0_9") (pintype "input"))
      (node (ref "E24") (pin "9") (pinfunction "I0_9") (pintype "input"))
      (node (ref "E39") (pin "13") (pinfunction "O_13") (pintype "output"))
    )
    (net (code "101") (name "Net-(E16D-I1)") (class "Default")
      (node (ref "E16") (pin "13") (pinfunction "I1_13") (pintype "input"))
      (node (ref "E24") (pin "8") (pinfunction "O_8") (pintype "output"))
    )
    (net (code "102") (name "Net-(E17B-I1)") (class "Default")
      (node (ref "E17") (pin "6") (pinfunction "I1_6") (pintype "input"))
      (node (ref "E21") (pin "9") (pinfunction "QC_9") (pintype "output"))
    )
    (net (code "103") (name "Net-(E17C-I1)") (class "Default")
      (node (ref "E17") (pin "9") (pinfunction "I1_9") (pintype "input"))
      (node (ref "E21") (pin "7") (pinfunction "QB_7") (pintype "output"))
    )
    (net (code "104") (name "Net-(E17D-I1)") (class "Default")
      (node (ref "E17") (pin "12") (pinfunction "I1_12") (pintype "input"))
      (node (ref "E21") (pin "5") (pinfunction "QA_5") (pintype "output"))
    )
    (net (code "105") (name "Net-(E18A-I0)") (class "Default")
      (node (ref "E18") (pin "2") (pinfunction "I0_2") (pintype "input"))
      (node (ref "E18") (pin "3") (pinfunction "I1_3") (pintype "input"))
      (node (ref "E32") (pin "5") (pinfunction "I_5") (pintype "input"))
      (node (ref "E35") (pin "3") (pinfunction "O_3") (pintype "output"))
      (node (ref "E38") (pin "1") (pinfunction "I_1") (pintype "input"))
    )
    (net (code "106") (name "Net-(E18B-I1)") (class "Default")
      (node (ref "E18") (pin "6") (pinfunction "I1_6") (pintype "input"))
      (node (ref "E22") (pin "9") (pinfunction "Q_9") (pintype "output"))
      (node (ref "E34") (pin "13") (pinfunction "I1_13") (pintype "input"))
    )
    (net (code "107") (name "Net-(E19A-I0)") (class "Default")
      (node (ref "E19") (pin "2") (pinfunction "I0_2") (pintype "input"))
      (node (ref "E20") (pin "12") (pinfunction "O_12") (pintype "output"))
    )
    (net (code "108") (name "Net-(E19B-I0)") (class "Default")
      (node (ref "E19") (pin "10") (pinfunction "O_10") (pintype "output"))
      (node (ref "E19") (pin "5") (pinfunction "I0_5") (pintype "input"))
    )
    (net (code "109") (name "Net-(E19B-O)") (class "Default")
      (node (ref "E19") (pin "4") (pinfunction "O_4") (pintype "output"))
      (node (ref "E22") (pin "1") (pinfunction "CLR_1") (pintype "input"))
    )
    (net (code "110") (name "Net-(E19D-I0)") (class "Default")
      (node (ref "E19") (pin "11") (pinfunction "I0_11") (pintype "input"))
      (node (ref "E20") (pin "8") (pinfunction "O_8") (pintype "output"))
    )
    (net (code "111") (name "Net-(E21A-SER)") (class "Default")
      (node (ref "E21") (pin "4") (pinfunction "SER_4") (pintype "input"))
      (node (ref "E29") (pin "3") (pinfunction "I1_3") (pintype "input"))
      (node (ref "E33") (pin "11") (pinfunction "QD_11") (pintype "output"))
    )
    (net (code "112") (name "Net-(E22A-Q)") (class "Default")
      (node (ref "E22") (pin "12") (pinfunction "D_12") (pintype "input"))
      (node (ref "E22") (pin "5") (pinfunction "Q_5") (pintype "output"))
    )
    (net (code "113") (name "Net-(E23A-I0)") (class "Default")
      (node (ref "E23") (pin "13") (pinfunction "O_13") (pintype "output"))
      (node (ref "E23") (pin "2") (pinfunction "I0_2") (pintype "input"))
    )
    (net (code "114") (name "Net-(E23A-O)") (class "Default")
      (node (ref "E23") (pin "1") (pinfunction "O_1") (pintype "output"))
      (node (ref "E30") (pin "1") (pinfunction "CLR_1") (pintype "input"))
    )
    (net (code "115") (name "Net-(E23B-I0)") (class "Default")
      (node (ref "E23") (pin "10") (pinfunction "O_10") (pintype "output"))
      (node (ref "E23") (pin "5") (pinfunction "I0_5") (pintype "input"))
    )
    (net (code "116") (name "Net-(E23B-O)") (class "Default")
      (node (ref "E23") (pin "4") (pinfunction "O_4") (pintype "output"))
      (node (ref "E26") (pin "1") (pinfunction "CLR_1") (pintype "input"))
    )
    (net (code "117") (name "Net-(E24A-I1)") (class "Default")
      (node (ref "E24") (pin "2") (pinfunction "I1_2") (pintype "input"))
      (node (ref "E7") (pin "5") (pinfunction "Q_5") (pintype "output"))
    )
    (net (code "118") (name "Net-(E24B-I0)") (class "Default")
      (node (ref "E24") (pin "4") (pinfunction "I0_4") (pintype "input"))
      (node (ref "E28") (pin "8") (pinfunction "O_8") (pintype "output"))
    )
    (net (code "119") (name "Net-(E24B-I1)") (class "Default")
      (node (ref "E24") (pin "5") (pinfunction "I1_5") (pintype "input"))
      (node (ref "E28") (pin "6") (pinfunction "O_6") (pintype "output"))
    )
    (net (code "120") (name "Net-(E24D-O)") (class "Default")
      (node (ref "E24") (pin "11") (pinfunction "O_11") (pintype "output"))
      (node (ref "E3") (pin "10") (pinfunction "I1_10") (pintype "input"))
    )
    (net (code "121") (name "Net-(E26A-Q)") (class "Default")
      (node (ref "E26") (pin "12") (pinfunction "D_12") (pintype "input"))
      (node (ref "E26") (pin "5") (pinfunction "Q_5") (pintype "output"))
    )
    (net (code "122") (name "Net-(E26B-Q)") (class "Default")
      (node (ref "E26") (pin "9") (pinfunction "Q_9") (pintype "output"))
      (node (ref "E34") (pin "1") (pinfunction "I0_1") (pintype "input"))
    )
    (net (code "123") (name "Net-(E27A-CLR)") (class "Default")
      (node (ref "E27") (pin "3") (pinfunction "CLR_3") (pintype "input"))
      (node (ref "E6") (pin "13") (pinfunction "O_13") (pintype "output"))
    )
    (net (code "124") (name "Net-(E29B-I1)") (class "Default")
      (node (ref "E29") (pin "6") (pinfunction "I1_6") (pintype "input"))
      (node (ref "E33") (pin "9") (pinfunction "QC_9") (pintype "output"))
    )
    (net (code "125") (name "Net-(E29C-I1)") (class "Default")
      (node (ref "E29") (pin "9") (pinfunction "I1_9") (pintype "input"))
      (node (ref "E33") (pin "7") (pinfunction "QB_7") (pintype "output"))
    )
    (net (code "126") (name "Net-(E29D-I1)") (class "Default")
      (node (ref "E29") (pin "12") (pinfunction "I1_12") (pintype "input"))
      (node (ref "E33") (pin "5") (pinfunction "QA_5") (pintype "output"))
    )
    (net (code "127") (name "Net-(E30A-Q)") (class "Default")
      (node (ref "E30") (pin "12") (pinfunction "D_12") (pintype "input"))
      (node (ref "E30") (pin "5") (pinfunction "Q_5") (pintype "output"))
    )
    (net (code "128") (name "Net-(E30B-Q)") (class "Default")
      (node (ref "E30") (pin "9") (pinfunction "Q_9") (pintype "output"))
      (node (ref "E34") (pin "10") (pinfunction "I1_10") (pintype "input"))
    )
    (net (code "129") (name "Net-(E34A-I1)") (class "Default")
      (node (ref "E34") (pin "2") (pinfunction "I1_2") (pintype "input"))
      (node (ref "E38") (pin "8") (pinfunction "O_8") (pintype "output"))
    )
    (net (code "130") (name "Net-(E34C-I0)") (class "Default")
      (node (ref "E34") (pin "9") (pinfunction "I0_9") (pintype "input"))
      (node (ref "E38") (pin "12") (pinfunction "O_12") (pintype "output"))
    )
    (net (code "131") (name "Net-(E34D-I0)") (class "Default")
      (node (ref "E34") (pin "12") (pinfunction "I0_12") (pintype "input"))
      (node (ref "E38") (pin "10") (pinfunction "O_10") (pintype "output"))
    )
    (net (code "132") (name "Net-(E35E-I3)") (class "Default")
      (node (ref "E35") (pin "9") (pinfunction "I3_9") (pintype "input"))
      (node (ref "E39") (pin "2") (pinfunction "O_2") (pintype "output"))
      (node (ref "E40") (pin "7") (pinfunction "FORCE0_7") (pintype "input"))
    )
    (net (code "133") (name "Net-(E35E-I4)") (class "Default")
      (node (ref "E31") (pin "11") (pinfunction "11_11") (pintype "passive"))
      (node (ref "E31") (pin "14") (pinfunction "14_14") (pintype "passive"))
      (node (ref "E35") (pin "10") (pinfunction "I4_10") (pintype "input"))
    )
    (net (code "134") (name "Net-(E35E-I5)") (class "Default")
      (node (ref "E31") (pin "12") (pinfunction "12_12") (pintype "passive"))
      (node (ref "E31") (pin "15") (pinfunction "15_15") (pintype "passive"))
      (node (ref "E35") (pin "11") (pinfunction "I5_11") (pintype "input"))
    )
    (net (code "135") (name "Net-(E35E-I6)") (class "Default")
      (node (ref "E31") (pin "13") (pinfunction "13_13") (pintype "passive"))
      (node (ref "E31") (pin "16") (pinfunction "16_16") (pintype "passive"))
      (node (ref "E35") (pin "12") (pinfunction "I6_12") (pintype "input"))
    )
    (net (code "136") (name "Net-(E38A-O)") (class "Default")
      (node (ref "E38") (pin "2") (pinfunction "O_2") (pintype "output"))
      (node (ref "E40") (pin "9") (pinfunction "FORCE0_9") (pintype "input"))
      (node (ref "E41") (pin "12") (pinfunction "D_12") (pintype "input"))
    )
    (net (code "137") (name "Net-(E40A-A1)") (class "Default")
      (node (ref "E31") (pin "1") (pinfunction "1_1") (pintype "passive"))
      (node (ref "E40") (pin "2") (pinfunction "A1_2") (pintype "output"))
    )
    (net (code "138") (name "Net-(E40A-A2)") (class "Default")
      (node (ref "E31") (pin "2") (pinfunction "2_2") (pintype "passive"))
      (node (ref "E40") (pin "4") (pinfunction "A2_4") (pintype "output"))
    )
    (net (code "139") (name "Net-(E40A-A3)") (class "Default")
      (node (ref "E31") (pin "3") (pinfunction "3_3") (pintype "passive"))
      (node (ref "E40") (pin "6") (pinfunction "A3_6") (pintype "output"))
    )
    (net (code "140") (name "Net-(E40B-A1)") (class "Default")
      (node (ref "E40") (pin "10") (pinfunction "A1_10") (pintype "output"))
      (node (ref "E41") (pin "15") (pinfunction "A_15") (pintype "input"))
    )
    (net (code "141") (name "Net-(E40B-A2)") (class "Default")
      (node (ref "E40") (pin "12") (pinfunction "A2_12") (pintype "output"))
      (node (ref "E41") (pin "14") (pinfunction "B_14") (pintype "input"))
    )
    (net (code "142") (name "Net-(E40B-A3)") (class "Default")
      (node (ref "E40") (pin "14") (pinfunction "A3_14") (pintype "output"))
      (node (ref "E41") (pin "13") (pinfunction "C_13") (pintype "input"))
    )
    (net (code "143") (name "Net-(IC1D-I)") (class "Default")
      (node (ref "IC1") (pin "12") (pinfunction "O_12") (pintype "output"))
      (node (ref "IC1") (pin "9") (pinfunction "I_9") (pintype "input"))
    )
    (net (code "144") (name "Net-(IC4A-I0)") (class "Default")
      (node (ref "IC4") (pin "1") (pinfunction "I0_1") (pintype "input"))
      (node (ref "IC4") (pin "11") (pinfunction "O_11") (pintype "output"))
    )
    (net (code "145") (name "Net-(IC5A-O)") (class "Default")
      (node (ref "IC5") (pin "1") (pinfunction "O_1") (pintype "output"))
      (node (ref "IC7") (pin "1") (pinfunction "I_1") (pintype "input"))
    )
    (net (code "146") (name "Net-(IC5B-O)") (class "Default")
      (node (ref "IC5") (pin "4") (pinfunction "O_4") (pintype "output"))
      (node (ref "IC7") (pin "3") (pinfunction "I_3") (pintype "input"))
    )
    (net (code "147") (name "Net-(IC5C-O)") (class "Default")
      (node (ref "IC5") (pin "10") (pinfunction "O_10") (pintype "output"))
      (node (ref "IC7") (pin "5") (pinfunction "I_5") (pintype "input"))
    )
    (net (code "148") (name "Net-(IC5D-O)") (class "Default")
      (node (ref "IC5") (pin "13") (pinfunction "O_13") (pintype "output"))
      (node (ref "IC7") (pin "9") (pinfunction "I_9") (pintype "input"))
    )
    (net (code "149") (name "Net-(IC6A-O)") (class "Default")
      (node (ref "IC6") (pin "1") (pinfunction "O_1") (pintype "output"))
      (node (ref "IC7") (pin "11") (pinfunction "I_11") (pintype "input"))
    )
    (net (code "150") (name "Net-(IC6B-O)") (class "Default")
      (node (ref "IC6") (pin "4") (pinfunction "O_4") (pintype "output"))
      (node (ref "IC7") (pin "13") (pinfunction "I_13") (pintype "input"))
    )
    (net (code "151") (name "Net-(IC10A-I)") (class "Default")
      (node (ref "IC10") (pin "1") (pinfunction "I_1") (pintype "input"))
      (node (ref "IC8") (pin "1") (pinfunction "O_1") (pintype "output"))
    )
    (net (code "152") (name "Net-(IC10B-I)") (class "Default")
      (node (ref "IC10") (pin "3") (pinfunction "I_3") (pintype "input"))
      (node (ref "IC8") (pin "4") (pinfunction "O_4") (pintype "output"))
    )
    (net (code "153") (name "Net-(IC10C-I)") (class "Default")
      (node (ref "IC10") (pin "5") (pinfunction "I_5") (pintype "input"))
      (node (ref "IC8") (pin "10") (pinfunction "O_10") (pintype "output"))
    )
    (net (code "154") (name "Net-(IC10D-I)") (class "Default")
      (node (ref "IC10") (pin "9") (pinfunction "I_9") (pintype "input"))
      (node (ref "IC8") (pin "13") (pinfunction "O_13") (pintype "output"))
    )
    (net (code "155") (name "Net-(IC10E-I)") (class "Default")
      (node (ref "IC10") (pin "11") (pinfunction "I_11") (pintype "input"))
      (node (ref "IC6") (pin "10") (pinfunction "O_10") (pintype "output"))
    )
    (net (code "156") (name "Net-(IC10F-I)") (class "Default")
      (node (ref "IC10") (pin "13") (pinfunction "I_13") (pintype "input"))
      (node (ref "IC6") (pin "13") (pinfunction "O_13") (pintype "output"))
    )
    (net (code "157") (name "Net-(IC19A-O)") (class "Default")
      (node (ref "IC19") (pin "2") (pinfunction "O_2") (pintype "output"))
      (node (ref "IC4") (pin "9") (pinfunction "I0_9") (pintype "input"))
    )
    (net (code "158") (name "Net-(IC19B-O)") (class "Default")
      (node (ref "IC19") (pin "4") (pinfunction "O_4") (pintype "output"))
      (node (ref "IC4") (pin "10") (pinfunction "I1_10") (pintype "input"))
    )
    (net (code "159") (name "Net-(IC19C-O)") (class "Default")
      (node (ref "IC19") (pin "6") (pinfunction "O_6") (pintype "output"))
      (node (ref "IC19") (pin "9") (pinfunction "I_9") (pintype "input"))
    )
    (net (code "160") (name "Net-(PAD10-P)") (class "Default")
      (node (ref "E13") (pin "1") (pinfunction "1_1") (pintype "passive"))
      (node (ref "PAD10") (pin "1") (pinfunction "P_1") (pintype "passive"))
    )
    (net (code "161") (name "Net-(PAD11-P)") (class "Default")
      (node (ref "E13") (pin "2") (pinfunction "2_2") (pintype "passive"))
      (node (ref "PAD11") (pin "1") (pinfunction "P_1") (pintype "passive"))
    )
    (net (code "162") (name "Net-(PAD12-P)") (class "Default")
      (node (ref "E13") (pin "3") (pinfunction "3_3") (pintype "passive"))
      (node (ref "PAD12") (pin "1") (pinfunction "P_1") (pintype "passive"))
    )
    (net (code "163") (name "Net-(PAD13-P)") (class "Default")
      (node (ref "E13") (pin "4") (pinfunction "4_4") (pintype "passive"))
      (node (ref "PAD13") (pin "1") (pinfunction "P_1") (pintype "passive"))
    )
    (net (code "164") (name "Net-(PAD14-P)") (class "Default")
      (node (ref "E13") (pin "5") (pinfunction "5_5") (pintype "passive"))
      (node (ref "PAD14") (pin "1") (pinfunction "P_1") (pintype "passive"))
    )
    (net (code "165") (name "Net-(PAD15-P)") (class "Default")
      (node (ref "E13") (pin "6") (pinfunction "6_6") (pintype "passive"))
      (node (ref "PAD15") (pin "1") (pinfunction "P_1") (pintype "passive"))
    )
    (net (code "166") (name "Net-(PAD16-P)") (class "Default")
      (node (ref "E13") (pin "7") (pinfunction "7_7") (pintype "passive"))
      (node (ref "PAD16") (pin "1") (pinfunction "P_1") (pintype "passive"))
    )
    (net (code "167") (name "Net-(PAD17-P)") (class "Default")
      (node (ref "E13") (pin "8") (pinfunction "8_8") (pintype "passive"))
      (node (ref "PAD17") (pin "1") (pinfunction "P_1") (pintype "passive"))
    )
    (net (code "168") (name "Net-(PAD20-P)") (class "Default")
      (node (ref "E13") (pin "16") (pinfunction "16_16") (pintype "passive"))
      (node (ref "PAD20") (pin "1") (pinfunction "P_1") (pintype "passive"))
    )
    (net (code "169") (name "Net-(PAD21-P)") (class "Default")
      (node (ref "E13") (pin "15") (pinfunction "15_15") (pintype "passive"))
      (node (ref "PAD21") (pin "1") (pinfunction "P_1") (pintype "passive"))
    )
    (net (code "170") (name "Net-(PAD22-P)") (class "Default")
      (node (ref "E13") (pin "14") (pinfunction "14_14") (pintype "passive"))
      (node (ref "PAD22") (pin "1") (pinfunction "P_1") (pintype "passive"))
    )
    (net (code "171") (name "Net-(PAD23-P)") (class "Default")
      (node (ref "E13") (pin "13") (pinfunction "13_13") (pintype "passive"))
      (node (ref "PAD23") (pin "1") (pinfunction "P_1") (pintype "passive"))
    )
    (net (code "172") (name "Net-(PAD24-P)") (class "Default")
      (node (ref "E13") (pin "12") (pinfunction "12_12") (pintype "passive"))
      (node (ref "PAD24") (pin "1") (pinfunction "P_1") (pintype "passive"))
    )
    (net (code "173") (name "Net-(PAD25-P)") (class "Default")
      (node (ref "E13") (pin "11") (pinfunction "11_11") (pintype "passive"))
      (node (ref "PAD25") (pin "1") (pinfunction "P_1") (pintype "passive"))
    )
    (net (code "174") (name "Net-(PAD26-P)") (class "Default")
      (node (ref "E13") (pin "10") (pinfunction "10_10") (pintype "passive"))
      (node (ref "PAD26") (pin "1") (pinfunction "P_1") (pintype "passive"))
    )
    (net (code "175") (name "Net-(PAD27-P)") (class "Default")
      (node (ref "E13") (pin "9") (pinfunction "9_9") (pintype "passive"))
      (node (ref "PAD27") (pin "1") (pinfunction "P_1") (pintype "passive"))
    )
    (net (code "176") (name "PARITY") (class "Default")
      (node (ref "E24") (pin "13") (pinfunction "I1_13") (pintype "input"))
      (node (ref "E4") (pin "15") (pinfunction "RCO_15") (pintype "output"))
      (node (ref "E8") (pin "1") (pinfunction "I_1") (pintype "input"))
      (node (ref "U$2") (pin "AB1") (pinfunction "1_AB1") (pintype "bidirectional"))
    )
    (net (code "177") (name "POWEROK") (class "Default")
      (node (ref "B27") (pin "V2") (pinfunction "P$2_V2") (pintype "bidirectional"))
      (node (ref "R18") (pin "1") (pinfunction "1_1") (pintype "passive"))
    )
    (net (code "178") (name "RD") (class "Default")
      (node (ref "E20") (pin "10") (pinfunction "I1_10") (pintype "input"))
      (node (ref "E32") (pin "1") (pinfunction "I_1") (pintype "input"))
      (node (ref "E36") (pin "14") (pinfunction "A3_14") (pintype "output"))
    )
    (net (code "179") (name "RUN") (class "Default")
      (node (ref "E15") (pin "9") (pinfunction "Q_9") (pintype "output"))
      (node (ref "E18") (pin "11") (pinfunction "I0_11") (pintype "input"))
      (node (ref "E18") (pin "12") (pinfunction "I1_12") (pintype "input"))
      (node (ref "E6") (pin "11") (pinfunction "I0_11") (pintype "input"))
    )
    (net (code "180") (name "RX_DATA") (class "Default")
      (node (ref "E33") (pin "4") (pinfunction "SER_4") (pintype "input"))
      (node (ref "E36") (pin "10") (pinfunction "A1_10") (pintype "output"))
    )
    (net (code "181") (name "SHIFT") (class "Default")
      (node (ref "E19") (pin "3") (pinfunction "I1_3") (pintype "input"))
      (node (ref "E36") (pin "12") (pinfunction "A2_12") (pintype "output"))
    )
    (net (code "182") (name "STROBE") (class "Default")
      (node (ref "IC3") (pin "1") (pinfunction "CLR_1") (pintype "input"))
      (node (ref "IC4") (pin "4") (pinfunction "I0_4") (pintype "input"))
      (node (ref "IC4") (pin "5") (pinfunction "I1_5") (pintype "input"))
      (node (ref "IC9") (pin "12") (pinfunction "O_12") (pintype "output"))
    )
    (net (code "183") (name "T2") (class "Default")
      (node (ref "A04") (pin "T2") (pinfunction "P$2_T2") (pintype "bidirectional"))
      (node (ref "D04") (pin "T2") (pinfunction "P$2_T2") (pintype "bidirectional"))
    )
    (net (code "184") (name "TP3") (class "Default")
      (node (ref "E11") (pin "9") (pinfunction "I0_9") (pintype "input"))
      (node (ref "IC4") (pin "6") (pinfunction "O_6") (pintype "output"))
      (node (ref "U$2") (pin "CH2") (pinfunction "1_CH2") (pintype "bidirectional"))
    )
    (net (code "185") (name "TP4") (class "Default")
      (node (ref "A02") (pin "T2") (pinfunction "P$2_T2") (pintype "bidirectional"))
      (node (ref "C27") (pin "J2") (pinfunction "P$2_J2") (pintype "bidirectional"))
      (node (ref "D02") (pin "T2") (pinfunction "P$2_T2") (pintype "bidirectional"))
      (node (ref "E11") (pin "4") (pinfunction "I0_4") (pintype "input"))
      (node (ref "U$2") (pin "CJ2") (pinfunction "1_CJ2") (pintype "bidirectional"))
    )
    (net (code "186") (name "TWELVE") (class "Default")
      (node (ref "E10") (pin "13") (pinfunction "I2_13") (pintype "input"))
      (node (ref "E14") (pin "11") (pinfunction "I0_11") (pintype "input"))
      (node (ref "E14") (pin "8") (pinfunction "I0_8") (pintype "input"))
      (node (ref "E14") (pin "9") (pinfunction "I1_9") (pintype "input"))
      (node (ref "E16") (pin "1") (pinfunction "I0_1") (pintype "input"))
      (node (ref "E2") (pin "6") (pinfunction "~{Q}_6") (pintype "output"))
      (node (ref "E3") (pin "1") (pinfunction "I0_1") (pintype "input"))
    )
    (net (code "187") (name "V2") (class "Default")
      (node (ref "A04") (pin "V2") (pinfunction "P$2_V2") (pintype "bidirectional"))
      (node (ref "D04") (pin "V2") (pinfunction "P$2_V2") (pintype "bidirectional"))
    )
    (net (code "188") (name "VCC") (class "Default")
      (node (ref "C1") (pin "1") (pinfunction "1_1") (pintype "passive"))
      (node (ref "C10") (pin "1") (pinfunction "1_1") (pintype "passive"))
      (node (ref "C11") (pin "1") (pinfunction "1_1") (pintype "passive"))
      (node (ref "C12") (pin "1") (pinfunction "1_1") (pintype "passive"))
      (node (ref "C13") (pin "1") (pinfunction "1_1") (pintype "passive"))
      (node (ref "C14") (pin "1") (pinfunction "1_1") (pintype "passive"))
      (node (ref "C15") (pin "1") (pinfunction "1_1") (pintype "passive"))
      (node (ref "C16") (pin "1") (pinfunction "1_1") (pintype "passive"))
      (node (ref "C17") (pin "1") (pinfunction "1_1") (pintype "passive"))
      (node (ref "C18") (pin "1") (pinfunction "1_1") (pintype "passive"))
      (node (ref "C19") (pin "1") (pinfunction "1_1") (pintype "passive"))
      (node (ref "C2") (pin "1") (pinfunction "1_1") (pintype "passive"))
      (node (ref "C20") (pin "1") (pinfunction "1_1") (pintype "passive"))
      (node (ref "C21") (pin "1") (pinfunction "1_1") (pintype "passive"))
      (node (ref "C22") (pin "1") (pinfunction "1_1") (pintype "passive"))
      (node (ref "C23") (pin "1") (pinfunction "1_1") (pintype "passive"))
      (node (ref "C24") (pin "1") (pinfunction "1_1") (pintype "passive"))
      (node (ref "C25") (pin "1") (pinfunction "1_1") (pintype "passive"))
      (node (ref "C26") (pin "1") (pinfunction "1_1") (pintype "passive"))
      (node (ref "C27A") (pin "1") (pinfunction "1_1") (pintype "passive"))
      (node (ref "C28") (pin "1") (pinfunction "1_1") (pintype "passive"))
      (node (ref "C29") (pin "1") (pinfunction "1_1") (pintype "passive"))
      (node (ref "C3") (pin "1") (pinfunction "1_1") (pintype "passive"))
      (node (ref "C30") (pin "1") (pinfunction "1_1") (pintype "passive"))
      (node (ref "C31") (pin "1") (pinfunction "1_1") (pintype "passive"))
      (node (ref "C32") (pin "1") (pinfunction "1_1") (pintype "passive"))
      (node (ref "C33") (pin "1") (pinfunction "1_1") (pintype "passive"))
      (node (ref "C34") (pin "1") (pinfunction "1_1") (pintype "passive"))
      (node (ref "C35") (pin "1") (pinfunction "1_1") (pintype "passive"))
      (node (ref "C36") (pin "1") (pinfunction "1_1") (pintype "passive"))
      (node (ref "C37") (pin "1") (pinfunction "1_1") (pintype "passive"))
      (node (ref "C38") (pin "1") (pinfunction "1_1") (pintype "passive"))
      (node (ref "C39") (pin "1") (pinfunction "1_1") (pintype "passive"))
      (node (ref "C4") (pin "1") (pinfunction "1_1") (pintype "passive"))
      (node (ref "C40") (pin "1") (pinfunction "1_1") (pintype "passive"))
      (node (ref "C41") (pin "1") (pinfunction "1_1") (pintype "passive"))
      (node (ref "C42") (pin "+") (pinfunction "+_+") (pintype "passive"))
      (node (ref "C43") (pin "+") (pinfunction "+_+") (pintype "passive"))
      (node (ref "C44") (pin "+") (pinfunction "+_+") (pintype "passive"))
      (node (ref "C45") (pin "+") (pinfunction "+_+") (pintype "passive"))
      (node (ref "C5") (pin "1") (pinfunction "1_1") (pintype "passive"))
      (node (ref "C6") (pin "1") (pinfunction "1_1") (pintype "passive"))
      (node (ref "C7") (pin "1") (pinfunction "1_1") (pintype "passive"))
      (node (ref "C8") (pin "1") (pinfunction "1_1") (pintype "passive"))
      (node (ref "C9") (pin "1") (pinfunction "1_1") (pintype "passive"))
      (node (ref "IC3") (pin "4") (pinfunction "PRE_4") (pintype "input"))
      (node (ref "R1") (pin "2") (pinfunction "2_2") (pintype "passive"))
      (node (ref "R18") (pin "2") (pinfunction "2_2") (pintype "passive"))
      (node (ref "R19") (pin "1") (pinfunction "1_1") (pintype "passive"))
      (node (ref "R2") (pin "2") (pinfunction "2_2") (pintype "passive"))
      (node (ref "R20") (pin "2") (pinfunction "2_2") (pintype "passive"))
      (node (ref "R25") (pin "1") (pinfunction "1_1") (pintype "passive"))
      (node (ref "R26") (pin "1") (pinfunction "1_1") (pintype "passive"))
      (node (ref "R27") (pin "1") (pinfunction "1_1") (pintype "passive"))
      (node (ref "R28") (pin "1") (pinfunction "1_1") (pintype "passive"))
      (node (ref "R29") (pin "1") (pinfunction "1_1") (pintype "passive"))
      (node (ref "R3") (pin "2") (pinfunction "2_2") (pintype "passive"))
      (node (ref "R30") (pin "1") (pinfunction "1_1") (pintype "passive"))
      (node (ref "R31") (pin "1") (pinfunction "1_1") (pintype "passive"))
      (node (ref "R32") (pin "1") (pinfunction "1_1") (pintype "passive"))
      (node (ref "R33") (pin "1") (pinfunction "1_1") (pintype "passive"))
      (node (ref "R34") (pin "1") (pinfunction "1_1") (pintype "passive"))
      (node (ref "R35") (pin "1") (pinfunction "1_1") (pintype "passive"))
      (node (ref "R36") (pin "1") (pinfunction "1_1") (pintype "passive"))
      (node (ref "R37") (pin "1") (pinfunction "1_1") (pintype "passive"))
      (node (ref "R38") (pin "1") (pinfunction "1_1") (pintype "passive"))
      (node (ref "R39") (pin "1") (pinfunction "1_1") (pintype "passive"))
      (node (ref "R4") (pin "2") (pinfunction "2_2") (pintype "passive"))
      (node (ref "R40") (pin "1") (pinfunction "1_1") (pintype "passive"))
      (node (ref "R5") (pin "2") (pinfunction "2_2") (pintype "passive"))
      (node (ref "R6") (pin "2") (pinfunction "2_2") (pintype "passive"))
      (node (ref "R7") (pin "2") (pinfunction "2_2") (pintype "passive"))
      (node (ref "R8") (pin "2") (pinfunction "2_2") (pintype "passive"))
      (node (ref "R9") (pin "2") (pinfunction "2_2") (pintype "passive"))
      (node (ref "U$2") (pin "AA2") (pinfunction "1_AA2") (pintype "bidirectional"))
      (node (ref "U$2") (pin "BA2") (pinfunction "1_BA2") (pintype "bidirectional"))
      (node (ref "U$2") (pin "CA2") (pinfunction "1_CA2") (pintype "bidirectional"))
    )
    (net (code "189") (name "WRT") (class "Default")
      (node (ref "E10") (pin "5") (pinfunction "I2_5") (pintype "input"))
      (node (ref "E14") (pin "5") (pinfunction "I0_5") (pintype "input"))
      (node (ref "E24") (pin "10") (pinfunction "I1_10") (pintype "input"))
      (node (ref "E32") (pin "2") (pinfunction "O_2") (pintype "output"))
    )
    (net (code "190") (name "XFER_IOT") (class "Default")
      (node (ref "E10") (pin "1") (pinfunction "I0_1") (pintype "input"))
      (node (ref "E12") (pin "12") (pinfunction "I0_12") (pintype "input"))
      (node (ref "E28") (pin "9") (pinfunction "I0_9") (pintype "input"))
      (node (ref "E38") (pin "6") (pinfunction "O_6") (pintype "output"))
    )
    (net (code "191") (name "XFER_REQ") (class "Default")
      (node (ref "E30") (pin "3") (pinfunction "CLK_3") (pintype "input"))
      (node (ref "E36") (pin "4") (pinfunction "A2_4") (pintype "output"))
      (node (ref "E39") (pin "12") (pinfunction "I1_12") (pintype "input"))
    )
    (net (code "192") (name "unconnected-(E4A-QA-Pad14)") (class "Default")
      (node (ref "E4") (pin "14") (pinfunction "QA_14") (pintype "output"))
    )
    (net (code "193") (name "unconnected-(E4A-QB-Pad13)") (class "Default")
      (node (ref "E4") (pin "13") (pinfunction "QB_13") (pintype "output"))
    )
    (net (code "194") (name "unconnected-(E4A-QC-Pad12)") (class "Default")
      (node (ref "E4") (pin "12") (pinfunction "QC_12") (pintype "output"))
    )
    (net (code "195") (name "unconnected-(E4A-QD-Pad11)") (class "Default")
      (node (ref "E4") (pin "11") (pinfunction "QD_11") (pintype "output"))
    )
    (net (code "196") (name "unconnected-(E7A-~{Q}-Pad6)") (class "Default")
      (node (ref "E7") (pin "6") (pinfunction "~{Q}_6") (pintype "output"))
    )
    (net (code "197") (name "unconnected-(E9A-~{QD}-Pad12)") (class "Default")
      (node (ref "E9") (pin "12") (pinfunction "~{QD}_12") (pintype "output"))
    )
    (net (code "198") (name "unconnected-(E15A-~{Q}-Pad6)") (class "Default")
      (node (ref "E15") (pin "6") (pinfunction "~{Q}_6") (pintype "output"))
    )
    (net (code "199") (name "unconnected-(E15B-~{Q}-Pad8)") (class "Default")
      (node (ref "E15") (pin "8") (pinfunction "~{Q}_8") (pintype "output"))
    )
    (net (code "200") (name "unconnected-(E21A-~{QD}-Pad12)") (class "Default")
      (node (ref "E21") (pin "12") (pinfunction "~{QD}_12") (pintype "output"))
    )
    (net (code "201") (name "unconnected-(E22A-~{Q}-Pad6)") (class "Default")
      (node (ref "E22") (pin "6") (pinfunction "~{Q}_6") (pintype "output"))
    )
    (net (code "202") (name "unconnected-(E22B-~{Q}-Pad8)") (class "Default")
      (node (ref "E22") (pin "8") (pinfunction "~{Q}_8") (pintype "output"))
    )
    (net (code "203") (name "unconnected-(E26A-~{Q}-Pad6)") (class "Default")
      (node (ref "E26") (pin "6") (pinfunction "~{Q}_6") (pintype "output"))
    )
    (net (code "204") (name "unconnected-(E26B-~{Q}-Pad8)") (class "Default")
      (node (ref "E26") (pin "8") (pinfunction "~{Q}_8") (pintype "output"))
    )
    (net (code "205") (name "unconnected-(E27A-Q-Pad15)") (class "Default")
      (node (ref "E27") (pin "15") (pinfunction "Q_15") (pintype "output"))
    )
    (net (code "206") (name "unconnected-(E30A-~{Q}-Pad6)") (class "Default")
      (node (ref "E30") (pin "6") (pinfunction "~{Q}_6") (pintype "output"))
    )
    (net (code "207") (name "unconnected-(E30B-~{Q}-Pad8)") (class "Default")
      (node (ref "E30") (pin "8") (pinfunction "~{Q}_8") (pintype "output"))
    )
    (net (code "208") (name "unconnected-(E31-Pad7)") (class "Default")
      (node (ref "E31") (pin "7") (pinfunction "7_7") (pintype "passive"))
    )
    (net (code "209") (name "unconnected-(E31-Pad8)") (class "Default")
      (node (ref "E31") (pin "8") (pinfunction "8_8") (pintype "passive"))
    )
    (net (code "210") (name "unconnected-(E31-Pad9)") (class "Default")
      (node (ref "E31") (pin "9") (pinfunction "9_9") (pintype "passive"))
    )
    (net (code "211") (name "unconnected-(E31-Pad10)") (class "Default")
      (node (ref "E31") (pin "10") (pinfunction "10_10") (pintype "passive"))
    )
    (net (code "212") (name "unconnected-(E33A-~{QD}-Pad12)") (class "Default")
      (node (ref "E33") (pin "12") (pinfunction "~{QD}_12") (pintype "output"))
    )
    (net (code "213") (name "unconnected-(E41A-O0-Pad1)") (class "Default")
      (node (ref "E41") (pin "1") (pinfunction "O0_1") (pintype "output"))
    )
    (net (code "214") (name "unconnected-(E41A-O8-Pad10)") (class "Default")
      (node (ref "E41") (pin "10") (pinfunction "O8_10") (pintype "output"))
    )
    (net (code "215") (name "unconnected-(E41A-O9-Pad11)") (class "Default")
      (node (ref "E41") (pin "11") (pinfunction "O9_11") (pintype "output"))
    )
    (net (code "216") (name "unconnected-(IC3A-Q-Pad5)") (class "Default")
      (node (ref "IC3") (pin "5") (pinfunction "Q_5") (pintype "output"))
    )
    (net (code "217") (name "~{BINIT}") (class "Default")
      (node (ref "E15") (pin "1") (pinfunction "CLR_1") (pintype "input"))
      (node (ref "E22") (pin "13") (pinfunction "CLR_13") (pintype "input"))
      (node (ref "E26") (pin "13") (pinfunction "CLR_13") (pintype "input"))
      (node (ref "E30") (pin "13") (pinfunction "CLR_13") (pintype "input"))
      (node (ref "E32") (pin "4") (pinfunction "O_4") (pintype "output"))
    )
    (net (code "218") (name "~{BTS3}") (class "Default")
      (node (ref "IC1") (pin "10") (pinfunction "O_10") (pintype "output"))
      (node (ref "IC3") (pin "3") (pinfunction "CLK_3") (pintype "input"))
    )
    (net (code "219") (name "~{C0}") (class "Default")
      (node (ref "C27") (pin "E1") (pinfunction "P$2_E1") (pintype "bidirectional"))
      (node (ref "E14") (pin "1") (pinfunction "O_1") (pintype "open_collector"))
      (node (ref "IC19") (pin "3") (pinfunction "I_3") (pintype "input"))
      (node (ref "R25") (pin "2") (pinfunction "2_2") (pintype "passive"))
      (node (ref "U$2") (pin "CE1") (pinfunction "1_CE1") (pintype "bidirectional"))
    )
    (net (code "220") (name "~{C1}") (class "Default")
      (node (ref "C27") (pin "H1") (pinfunction "P$2_H1") (pintype "bidirectional"))
      (node (ref "E14") (pin "13") (pinfunction "O_13") (pintype "open_collector"))
      (node (ref "IC1") (pin "13") (pinfunction "I_13") (pintype "input"))
      (node (ref "IC19") (pin "5") (pinfunction "I_5") (pintype "input"))
      (node (ref "R26") (pin "2") (pinfunction "2_2") (pintype "passive"))
      (node (ref "U$2") (pin "CH1") (pinfunction "1_CH1") (pintype "bidirectional"))
    )
    (net (code "221") (name "~{CLK_BUF}") (class "Default")
      (node (ref "E21") (pin "6") (pinfunction "CLK_6") (pintype "input"))
      (node (ref "E33") (pin "6") (pinfunction "CLK_6") (pintype "input"))
      (node (ref "E8") (pin "12") (pinfunction "O_12") (pintype "output"))
      (node (ref "E9") (pin "6") (pinfunction "CLK_6") (pintype "input"))
    )
    (net (code "222") (name "~{CLK_PARITY}") (class "Default")
      (node (ref "E19") (pin "1") (pinfunction "O_1") (pintype "output"))
      (node (ref "E27") (pin "1") (pinfunction "CLK_1") (pintype "input"))
      (node (ref "E8") (pin "3") (pinfunction "I_3") (pintype "input"))
    )
    (net (code "223") (name "~{DATA0}") (class "Default")
      (node (ref "A27") (pin "R1") (pinfunction "P$2_R1") (pintype "bidirectional"))
      (node (ref "E1") (pin "15") (pinfunction "Y3_15") (pintype "input"))
      (node (ref "E42") (pin "3") (pinfunction "O_3") (pintype "open_collector"))
      (node (ref "E5") (pin "1") (pinfunction "O_1") (pintype "open_collector"))
      (node (ref "IC8") (pin "2") (pinfunction "I0_2") (pintype "input"))
      (node (ref "R27") (pin "2") (pinfunction "2_2") (pintype "passive"))
      (node (ref "U$2") (pin "AR1") (pinfunction "1_AR1") (pintype "bidirectional"))
    )
    (net (code "224") (name "~{DATA1}") (class "Default")
      (node (ref "A27") (pin "S1") (pinfunction "P$2_S1") (pintype "bidirectional"))
      (node (ref "E1") (pin "13") (pinfunction "Y2_13") (pintype "input"))
      (node (ref "E42") (pin "6") (pinfunction "O_6") (pintype "open_collector"))
      (node (ref "E5") (pin "4") (pinfunction "O_4") (pintype "open_collector"))
      (node (ref "IC8") (pin "5") (pinfunction "I0_5") (pintype "input"))
      (node (ref "R28") (pin "2") (pinfunction "2_2") (pintype "passive"))
      (node (ref "U$2") (pin "AS1") (pinfunction "1_AS1") (pintype "bidirectional"))
    )
    (net (code "225") (name "~{DATA2}") (class "Default")
      (node (ref "A27") (pin "U1") (pinfunction "P$2_U1") (pintype "bidirectional"))
      (node (ref "E1") (pin "11") (pinfunction "Y1_11") (pintype "input"))
      (node (ref "E42") (pin "8") (pinfunction "O_8") (pintype "open_collector"))
      (node (ref "E5") (pin "10") (pinfunction "O_10") (pintype "open_collector"))
      (node (ref "IC8") (pin "8") (pinfunction "I0_8") (pintype "input"))
      (node (ref "R29") (pin "2") (pinfunction "2_2") (pintype "passive"))
      (node (ref "U$2") (pin "AU1") (pinfunction "1_AU1") (pintype "bidirectional"))
    )
    (net (code "226") (name "~{DATA3}") (class "Default")
      (node (ref "A27") (pin "V1") (pinfunction "P$2_V1") (pintype "bidirectional"))
      (node (ref "E1") (pin "5") (pinfunction "Y3_5") (pintype "input"))
      (node (ref "E42") (pin "11") (pinfunction "O_11") (pintype "open_collector"))
      (node (ref "E5") (pin "13") (pinfunction "O_13") (pintype "open_collector"))
      (node (ref "IC8") (pin "11") (pinfunction "I0_11") (pintype "input"))
      (node (ref "R30") (pin "2") (pinfunction "2_2") (pintype "passive"))
      (node (ref "U$2") (pin "AV1") (pinfunction "1_AV1") (pintype "bidirectional"))
    )
    (net (code "227") (name "~{DATA4}") (class "Default")
      (node (ref "B27") (pin "R1") (pinfunction "P$2_R1") (pintype "bidirectional"))
      (node (ref "E1") (pin "3") (pinfunction "Y2_3") (pintype "input"))
      (node (ref "E17") (pin "1") (pinfunction "O_1") (pintype "open_collector"))
      (node (ref "E43") (pin "3") (pinfunction "O_3") (pintype "open_collector"))
      (node (ref "IC6") (pin "8") (pinfunction "I0_8") (pintype "input"))
      (node (ref "R31") (pin "2") (pinfunction "2_2") (pintype "passive"))
      (node (ref "U$2") (pin "BR1") (pinfunction "1_BR1") (pintype "bidirectional"))
    )
    (net (code "228") (name "~{DATA5}") (class "Default")
      (node (ref "B27") (pin "S1") (pinfunction "P$2_S1") (pintype "bidirectional"))
      (node (ref "E1") (pin "1") (pinfunction "Y1_1") (pintype "input"))
      (node (ref "E17") (pin "4") (pinfunction "O_4") (pintype "open_collector"))
      (node (ref "E43") (pin "6") (pinfunction "O_6") (pintype "open_collector"))
      (node (ref "IC6") (pin "11") (pinfunction "I0_11") (pintype "input"))
      (node (ref "R32") (pin "2") (pinfunction "2_2") (pintype "passive"))
      (node (ref "U$2") (pin "BS1") (pinfunction "1_BS1") (pintype "bidirectional"))
    )
    (net (code "229") (name "~{DATA6}") (class "Default")
      (node (ref "B27") (pin "U1") (pinfunction "P$2_U1") (pintype "bidirectional"))
      (node (ref "E17") (pin "10") (pinfunction "O_10") (pintype "open_collector"))
      (node (ref "E25") (pin "15") (pinfunction "Y3_15") (pintype "input"))
      (node (ref "E43") (pin "8") (pinfunction "O_8") (pintype "open_collector"))
      (node (ref "IC5") (pin "3") (pinfunction "I1_3") (pintype "input"))
      (node (ref "R35") (pin "2") (pinfunction "2_2") (pintype "passive"))
      (node (ref "U$2") (pin "BU1") (pinfunction "1_BU1") (pintype "bidirectional"))
    )
    (net (code "230") (name "~{DATA7}") (class "Default")
      (node (ref "B27") (pin "V1") (pinfunction "P$2_V1") (pintype "bidirectional"))
      (node (ref "E17") (pin "13") (pinfunction "O_13") (pintype "open_collector"))
      (node (ref "E25") (pin "13") (pinfunction "Y2_13") (pintype "input"))
      (node (ref "E43") (pin "11") (pinfunction "O_11") (pintype "open_collector"))
      (node (ref "IC5") (pin "5") (pinfunction "I0_5") (pintype "input"))
      (node (ref "R36") (pin "2") (pinfunction "2_2") (pintype "passive"))
      (node (ref "U$2") (pin "BV1") (pinfunction "1_BV1") (pintype "bidirectional"))
    )
    (net (code "231") (name "~{DATA8}") (class "Default")
      (node (ref "D27") (pin "R1") (pinfunction "P$2_R1") (pintype "bidirectional"))
      (node (ref "E25") (pin "11") (pinfunction "Y1_11") (pintype "input"))
      (node (ref "E29") (pin "1") (pinfunction "O_1") (pintype "open_collector"))
      (node (ref "E44") (pin "3") (pinfunction "O_3") (pintype "open_collector"))
      (node (ref "IC5") (pin "9") (pinfunction "I1_9") (pintype "input"))
      (node (ref "R37") (pin "2") (pinfunction "2_2") (pintype "passive"))
      (node (ref "U$2") (pin "DR1") (pinfunction "1_DR1") (pintype "bidirectional"))
    )
    (net (code "232") (name "~{DATA9}") (class "Default")
      (node (ref "D27") (pin "S1") (pinfunction "P$2_S1") (pintype "bidirectional"))
      (node (ref "E25") (pin "5") (pinfunction "Y3_5") (pintype "input"))
      (node (ref "E29") (pin "4") (pinfunction "O_4") (pintype "open_collector"))
      (node (ref "E44") (pin "6") (pinfunction "O_6") (pintype "open_collector"))
      (node (ref "IC5") (pin "11") (pinfunction "I0_11") (pintype "input"))
      (node (ref "R38") (pin "2") (pinfunction "2_2") (pintype "passive"))
      (node (ref "U$2") (pin "DS1") (pinfunction "1_DS1") (pintype "bidirectional"))
    )
    (net (code "233") (name "~{DATA10}") (class "Default")
      (node (ref "D27") (pin "U1") (pinfunction "P$2_U1") (pintype "bidirectional"))
      (node (ref "E25") (pin "3") (pinfunction "Y2_3") (pintype "input"))
      (node (ref "E29") (pin "10") (pinfunction "O_10") (pintype "open_collector"))
      (node (ref "E44") (pin "8") (pinfunction "O_8") (pintype "open_collector"))
      (node (ref "IC6") (pin "3") (pinfunction "I1_3") (pintype "input"))
      (node (ref "R39") (pin "2") (pinfunction "2_2") (pintype "passive"))
      (node (ref "U$2") (pin "DU1") (pinfunction "1_DU1") (pintype "bidirectional"))
    )
    (net (code "234") (name "~{DATA11}") (class "Default")
      (node (ref "D27") (pin "V1") (pinfunction "P$2_V1") (pintype "bidirectional"))
      (node (ref "E25") (pin "1") (pinfunction "Y1_1") (pintype "input"))
      (node (ref "E29") (pin "13") (pinfunction "O_13") (pintype "open_collector"))
      (node (ref "E44") (pin "11") (pinfunction "O_11") (pintype "open_collector"))
      (node (ref "IC6") (pin "5") (pinfunction "I0_5") (pintype "input"))
      (node (ref "R40") (pin "2") (pinfunction "2_2") (pintype "passive"))
      (node (ref "U$2") (pin "DV1") (pinfunction "1_DV1") (pintype "bidirectional"))
    )
    (net (code "235") (name "~{DONE_SKIP}") (class "Default")
      (node (ref "E10") (pin "11") (pinfunction "I2_11") (pintype "input"))
      (node (ref "E19") (pin "9") (pinfunction "I1_9") (pintype "input"))
      (node (ref "E34") (pin "11") (pinfunction "O_11") (pintype "output"))
      (node (ref "U$2") (pin "CB1") (pinfunction "1_CB1") (pintype "bidirectional"))
    )
    (net (code "236") (name "~{DONE}") (class "Default")
      (node (ref "E10") (pin "4") (pinfunction "I1_4") (pintype "input"))
      (node (ref "E28") (pin "10") (pinfunction "I1_10") (pintype "input"))
      (node (ref "E32") (pin "8") (pinfunction "O_8") (pintype "output"))
    )
    (net (code "237") (name "~{ENB_BUF_LD}") (class "Default")
      (node (ref "E16") (pin "11") (pinfunction "O_11") (pintype "output"))
      (node (ref "E20") (pin "13") (pinfunction "I2_13") (pintype "input"))
      (node (ref "E21") (pin "13") (pinfunction "SHF_13") (pintype "input"))
      (node (ref "E33") (pin "13") (pinfunction "SHF_13") (pintype "input"))
      (node (ref "E4") (pin "9") (pinfunction "LD_9") (pintype "input"))
      (node (ref "E9") (pin "13") (pinfunction "SHF_13") (pintype "input"))
    )
    (net (code "238") (name "~{ERR_SKIP}") (class "Default")
      (node (ref "E10") (pin "10") (pinfunction "I1_10") (pintype "input"))
      (node (ref "E23") (pin "9") (pinfunction "I1_9") (pintype "input"))
      (node (ref "E34") (pin "3") (pinfunction "O_3") (pintype "output"))
    )
    (net (code "239") (name "~{INIT_IOT}") (class "Default")
      (node (ref "E41") (pin "9") (pinfunction "O7_9") (pintype "output"))
      (node (ref "E7") (pin "2") (pinfunction "D_2") (pintype "input"))
    )
    (net (code "240") (name "~{INIT}") (class "Default")
      (node (ref "E16") (pin "10") (pinfunction "I1_10") (pintype "input"))
      (node (ref "E2") (pin "1") (pinfunction "CLR_1") (pintype "input"))
      (node (ref "E2") (pin "13") (pinfunction "CLR_13") (pintype "input"))
      (node (ref "E21") (pin "1") (pinfunction "CLR_1") (pintype "input"))
      (node (ref "E33") (pin "1") (pinfunction "CLR_1") (pintype "input"))
      (node (ref "E4") (pin "1") (pinfunction "CLR_1") (pintype "input"))
      (node (ref "E8") (pin "6") (pinfunction "O_6") (pintype "output"))
      (node (ref "E9") (pin "1") (pinfunction "CLR_1") (pintype "input"))
    )
    (net (code "241") (name "~{INTERNAL_IO}") (class "Default")
      (node (ref "E18") (pin "1") (pinfunction "O_1") (pintype "open_collector"))
      (node (ref "U$2") (pin "CL1") (pinfunction "1_CL1") (pintype "bidirectional"))
    )
    (net (code "242") (name "~{INTR_IOT}") (class "Default")
      (node (ref "E41") (pin "7") (pinfunction "O6_7") (pintype "output"))
      (node (ref "E6") (pin "6") (pinfunction "I1_6") (pintype "input"))
    )
    (net (code "243") (name "~{INT_RQST}") (class "Default")
      (node (ref "C27") (pin "P1") (pinfunction "P$2_P1") (pintype "bidirectional"))
      (node (ref "E18") (pin "4") (pinfunction "O_4") (pintype "open_collector"))
      (node (ref "IC2") (pin "3") (pinfunction "I_3") (pintype "input"))
      (node (ref "R34") (pin "2") (pinfunction "2_2") (pintype "passive"))
      (node (ref "U$2") (pin "CP1") (pinfunction "1_CP1") (pintype "bidirectional"))
    )
    (net (code "244") (name "~{IO_PAUSE}") (class "Default")
      (node (ref "C27") (pin "D1") (pinfunction "P$2_D1") (pintype "bidirectional"))
      (node (ref "E39") (pin "6") (pinfunction "I0_6") (pintype "input"))
      (node (ref "IC19") (pin "1") (pinfunction "I_1") (pintype "input"))
      (node (ref "IC3") (pin "6") (pinfunction "~{Q}_6") (pintype "output"))
      (node (ref "U$2") (pin "CD1") (pinfunction "1_CD1") (pintype "bidirectional"))
    )
    (net (code "245") (name "~{LCD_IOT}") (class "Default")
      (node (ref "E12") (pin "4") (pinfunction "I0_4") (pintype "input"))
      (node (ref "E16") (pin "5") (pinfunction "I1_5") (pintype "input"))
      (node (ref "E38") (pin "3") (pinfunction "I_3") (pintype "input"))
      (node (ref "E41") (pin "2") (pinfunction "O1_2") (pintype "output"))
      (node (ref "E6") (pin "3") (pinfunction "I1_3") (pintype "input"))
    )
    (net (code "246") (name "~{MAINT}") (class "Default")
      (node (ref "E10") (pin "3") (pinfunction "I0_3") (pintype "input"))
      (node (ref "E16") (pin "12") (pinfunction "I0_12") (pintype "input"))
      (node (ref "E2") (pin "8") (pinfunction "~{Q}_8") (pintype "output"))
      (node (ref "E22") (pin "4") (pinfunction "PRE_4") (pintype "input"))
      (node (ref "E26") (pin "4") (pinfunction "PRE_4") (pintype "input"))
      (node (ref "E28") (pin "1") (pinfunction "I0_1") (pintype "input"))
      (node (ref "E28") (pin "12") (pinfunction "I2_12") (pintype "input"))
      (node (ref "E30") (pin "4") (pinfunction "PRE_4") (pintype "input"))
      (node (ref "E32") (pin "11") (pinfunction "I_11") (pintype "input"))
    )
    (net (code "247") (name "~{MD03}") (class "Default")
      (node (ref "A03") (pin "H1") (pinfunction "P$2_H1") (pintype "bidirectional"))
      (node (ref "A27") (pin "P1") (pinfunction "P$2_P1") (pintype "bidirectional"))
      (node (ref "D03") (pin "H1") (pinfunction "P$2_H1") (pintype "bidirectional"))
      (node (ref "E35") (pin "4") (pinfunction "I0_4") (pintype "input"))
      (node (ref "U$2") (pin "AP1") (pinfunction "1_AP1") (pintype "bidirectional"))
    )
    (net (code "248") (name "~{MD04}") (class "Default")
      (node (ref "A03") (pin "L1") (pinfunction "P$2_L1") (pintype "bidirectional"))
      (node (ref "B27") (pin "K1") (pinfunction "P$2_K1") (pintype "bidirectional"))
      (node (ref "D03") (pin "L1") (pinfunction "P$2_L1") (pintype "bidirectional"))
      (node (ref "E35") (pin "6") (pinfunction "I2_6") (pintype "input"))
      (node (ref "U$2") (pin "BK1") (pinfunction "1_BK1") (pintype "bidirectional"))
    )
    (net (code "249") (name "~{MD05}") (class "Default")
      (node (ref "A03") (pin "P1") (pinfunction "P$2_P1") (pintype "bidirectional"))
      (node (ref "B27") (pin "L1") (pinfunction "P$2_L1") (pintype "bidirectional"))
      (node (ref "D03") (pin "P1") (pinfunction "P$2_P1") (pintype "bidirectional"))
      (node (ref "E35") (pin "5") (pinfunction "I1_5") (pintype "input"))
      (node (ref "U$2") (pin "BL1") (pinfunction "1_BL1") (pintype "bidirectional"))
    )
    (net (code "250") (name "~{MD06}") (class "Default")
      (node (ref "A03") (pin "D2") (pinfunction "P$2_D2") (pintype "bidirectional"))
      (node (ref "B27") (pin "M1") (pinfunction "P$2_M1") (pintype "bidirectional"))
      (node (ref "D03") (pin "D2") (pinfunction "P$2_D2") (pintype "bidirectional"))
      (node (ref "E31") (pin "4") (pinfunction "4_4") (pintype "passive"))
      (node (ref "E40") (pin "1") (pinfunction "Y1_1") (pintype "input"))
      (node (ref "U$2") (pin "BM1") (pinfunction "1_BM1") (pintype "bidirectional"))
    )
    (net (code "251") (name "~{MD07}") (class "Default")
      (node (ref "A03") (pin "H2") (pinfunction "P$2_H2") (pintype "bidirectional"))
      (node (ref "B27") (pin "P1") (pinfunction "P$2_P1") (pintype "bidirectional"))
      (node (ref "D03") (pin "H2") (pinfunction "P$2_H2") (pintype "bidirectional"))
      (node (ref "E31") (pin "5") (pinfunction "5_5") (pintype "passive"))
      (node (ref "E40") (pin "3") (pinfunction "Y2_3") (pintype "input"))
      (node (ref "U$2") (pin "BP1") (pinfunction "1_BP1") (pintype "bidirectional"))
    )
    (net (code "252") (name "~{MD08}") (class "Default")
      (node (ref "A03") (pin "M2") (pinfunction "P$2_M2") (pintype "bidirectional"))
      (node (ref "D03") (pin "M2") (pinfunction "P$2_M2") (pintype "bidirectional"))
      (node (ref "D27") (pin "K1") (pinfunction "P$2_K1") (pintype "bidirectional"))
      (node (ref "E31") (pin "6") (pinfunction "6_6") (pintype "passive"))
      (node (ref "E40") (pin "5") (pinfunction "Y3_5") (pintype "input"))
      (node (ref "U$2") (pin "DK1") (pinfunction "1_DK1") (pintype "bidirectional"))
    )
    (net (code "253") (name "~{MD09}") (class "Default")
      (node (ref "D27") (pin "L1") (pinfunction "P$2_L1") (pintype "bidirectional"))
      (node (ref "E40") (pin "15") (pinfunction "Y3_15") (pintype "input"))
      (node (ref "IC1") (pin "2") (pinfunction "O_2") (pintype "output"))
      (node (ref "U$2") (pin "DL1") (pinfunction "1_DL1") (pintype "bidirectional"))
    )
    (net (code "254") (name "~{MD10}") (class "Default")
      (node (ref "D27") (pin "M1") (pinfunction "P$2_M1") (pintype "bidirectional"))
      (node (ref "E40") (pin "13") (pinfunction "Y2_13") (pintype "input"))
      (node (ref "IC1") (pin "4") (pinfunction "O_4") (pintype "output"))
      (node (ref "U$2") (pin "DM1") (pinfunction "1_DM1") (pintype "bidirectional"))
    )
    (net (code "255") (name "~{MD11}") (class "Default")
      (node (ref "D27") (pin "P1") (pinfunction "P$2_P1") (pintype "bidirectional"))
      (node (ref "E40") (pin "11") (pinfunction "Y1_11") (pintype "input"))
      (node (ref "IC1") (pin "6") (pinfunction "O_6") (pintype "output"))
      (node (ref "U$2") (pin "DP1") (pinfunction "1_DP1") (pintype "bidirectional"))
    )
    (net (code "256") (name "~{PARITY}") (class "Default")
      (node (ref "E24") (pin "12") (pinfunction "I0_12") (pintype "input"))
      (node (ref "E27") (pin "14") (pinfunction "~{Q}_14") (pintype "output"))
    )
    (net (code "257") (name "~{RX8_SEL}") (class "Default")
      (node (ref "E1") (pin "7") (pinfunction "FORCE0_7") (pintype "input"))
      (node (ref "E1") (pin "9") (pinfunction "FORCE0_9") (pintype "input"))
      (node (ref "E25") (pin "7") (pinfunction "FORCE0_7") (pintype "input"))
      (node (ref "E25") (pin "9") (pinfunction "FORCE0_9") (pintype "input"))
      (node (ref "E32") (pin "6") (pinfunction "O_6") (pintype "output"))
    )
    (net (code "258") (name "~{RX_12_BIT}") (class "Default")
      (node (ref "DRIVE") (pin "FF") (pinfunction "28_FF") (pintype "bidirectional"))
      (node (ref "E14") (pin "10") (pinfunction "O_10") (pintype "open_collector"))
      (node (ref "R16") (pin "2") (pinfunction "2_2") (pintype "passive"))
      (node (ref "R7") (pin "1") (pinfunction "1_1") (pintype "passive"))
    )
    (net (code "259") (name "~{RX_DATA}") (class "Default")
      (node (ref "DRIVE") (pin "BB") (pinfunction "24_BB") (pintype "bidirectional"))
      (node (ref "E14") (pin "4") (pinfunction "O_4") (pintype "open_collector"))
      (node (ref "E36") (pin "11") (pinfunction "Y1_11") (pintype "input"))
      (node (ref "R17") (pin "2") (pinfunction "2_2") (pintype "passive"))
      (node (ref "R8") (pin "1") (pinfunction "1_1") (pintype "passive"))
    )
    (net (code "260") (name "~{RX_DONE}") (class "Default")
      (node (ref "DRIVE") (pin "X") (pinfunction "20_X") (pintype "bidirectional"))
      (node (ref "E36") (pin "5") (pinfunction "Y3_5") (pintype "input"))
      (node (ref "R13") (pin "2") (pinfunction "2_2") (pintype "passive"))
      (node (ref "R4") (pin "1") (pinfunction "1_1") (pintype "passive"))
    )
    (net (code "261") (name "~{RX_ERROR}") (class "Default")
      (node (ref "DRIVE") (pin "J") (pinfunction "8_J") (pintype "bidirectional"))
      (node (ref "E36") (pin "1") (pinfunction "Y1_1") (pintype "input"))
      (node (ref "R14") (pin "2") (pinfunction "2_2") (pintype "passive"))
      (node (ref "R5") (pin "1") (pinfunction "1_1") (pintype "passive"))
    )
    (net (code "262") (name "~{RX_INIT}") (class "Default")
      (node (ref "DRIVE") (pin "N") (pinfunction "12_N") (pintype "bidirectional"))
      (node (ref "E37") (pin "13") (pinfunction "O_13") (pintype "open_collector"))
      (node (ref "R9") (pin "1") (pinfunction "1_1") (pintype "passive"))
    )
    (net (code "263") (name "~{RX_OUT}") (class "Default")
      (node (ref "DRIVE") (pin "RR") (pinfunction "36_RR") (pintype "bidirectional"))
      (node (ref "E36") (pin "15") (pinfunction "Y3_15") (pintype "input"))
      (node (ref "R12") (pin "2") (pinfunction "2_2") (pintype "passive"))
      (node (ref "R3") (pin "1") (pinfunction "1_1") (pintype "passive"))
    )
    (net (code "264") (name "~{RX_RUN}") (class "Default")
      (node (ref "DRIVE") (pin "D") (pinfunction "4_D") (pintype "bidirectional"))
      (node (ref "E18") (pin "13") (pinfunction "O_13") (pintype "open_collector"))
      (node (ref "R15") (pin "2") (pinfunction "2_2") (pintype "passive"))
      (node (ref "R6") (pin "1") (pinfunction "1_1") (pintype "passive"))
    )
    (net (code "265") (name "~{RX_SHIFT}") (class "Default")
      (node (ref "DRIVE") (pin "LL") (pinfunction "32_LL") (pintype "bidirectional"))
      (node (ref "E36") (pin "13") (pinfunction "Y2_13") (pintype "input"))
      (node (ref "R10") (pin "2") (pinfunction "2_2") (pintype "passive"))
      (node (ref "R2") (pin "1") (pinfunction "1_1") (pintype "passive"))
    )
    (net (code "266") (name "~{RX_TR_REQ}") (class "Default")
      (node (ref "DRIVE") (pin "T") (pinfunction "16_T") (pintype "bidirectional"))
      (node (ref "E36") (pin "3") (pinfunction "Y2_3") (pintype "input"))
      (node (ref "R1") (pin "1") (pinfunction "1_1") (pintype "passive"))
      (node (ref "R11") (pin "2") (pinfunction "2_2") (pintype "passive"))
    )
    (net (code "267") (name "~{SDN_IOT}") (class "Default")
      (node (ref "E38") (pin "11") (pinfunction "I_11") (pintype "input"))
      (node (ref "E41") (pin "6") (pinfunction "O5_6") (pintype "output"))
    )
    (net (code "268") (name "~{SER_IOT}") (class "Default")
      (node (ref "E38") (pin "9") (pinfunction "I_9") (pintype "input"))
      (node (ref "E41") (pin "5") (pinfunction "O4_5") (pintype "output"))
    )
    (net (code "269") (name "~{SKIP}") (class "Default")
      (node (ref "C27") (pin "S1") (pinfunction "P$2_S1") (pintype "bidirectional"))
      (node (ref "E18") (pin "10") (pinfunction "O_10") (pintype "open_collector"))
      (node (ref "IC2") (pin "1") (pinfunction "I_1") (pintype "input"))
      (node (ref "R33") (pin "2") (pinfunction "2_2") (pintype "passive"))
      (node (ref "U$2") (pin "CS1") (pinfunction "1_CS1") (pintype "bidirectional"))
    )
    (net (code "270") (name "~{STR_IOT}") (class "Default")
      (node (ref "E38") (pin "13") (pinfunction "I_13") (pintype "input"))
      (node (ref "E41") (pin "4") (pinfunction "O3_4") (pintype "output"))
    )
    (net (code "271") (name "~{TP3}") (class "Default")
      (node (ref "E11") (pin "14") (pinfunction "O_14") (pintype "output"))
      (node (ref "E19") (pin "8") (pinfunction "I0_8") (pintype "input"))
      (node (ref "E20") (pin "1") (pinfunction "I0_1") (pintype "input"))
      (node (ref "E23") (pin "11") (pinfunction "I0_11") (pintype "input"))
      (node (ref "E23") (pin "8") (pinfunction "I0_8") (pintype "input"))
      (node (ref "E32") (pin "13") (pinfunction "I_13") (pintype "input"))
      (node (ref "E6") (pin "2") (pinfunction "I0_2") (pintype "input"))
      (node (ref "E6") (pin "5") (pinfunction "I0_5") (pintype "input"))
    )
    (net (code "272") (name "~{TR_SKIP}") (class "Default")
      (node (ref "E10") (pin "9") (pinfunction "I0_9") (pintype "input"))
      (node (ref "E23") (pin "12") (pinfunction "I1_12") (pintype "input"))
      (node (ref "E34") (pin "8") (pinfunction "O_8") (pintype "output"))
      (node (ref "U$2") (pin "DB1") (pinfunction "1_DB1") (pintype "bidirectional"))
    )
    (net (code "273") (name "~{XFER_IOT}") (class "Default")
      (node (ref "E16") (pin "4") (pinfunction "I0_4") (pintype "input"))
      (node (ref "E19") (pin "12") (pinfunction "I1_12") (pintype "input"))
      (node (ref "E38") (pin "5") (pinfunction "I_5") (pintype "input"))
      (node (ref "E41") (pin "3") (pinfunction "O2_3") (pintype "output"))
    )
  )
)
